# io-board-f-6.net
KiCad netlist of a schematic drawn in EAGLE
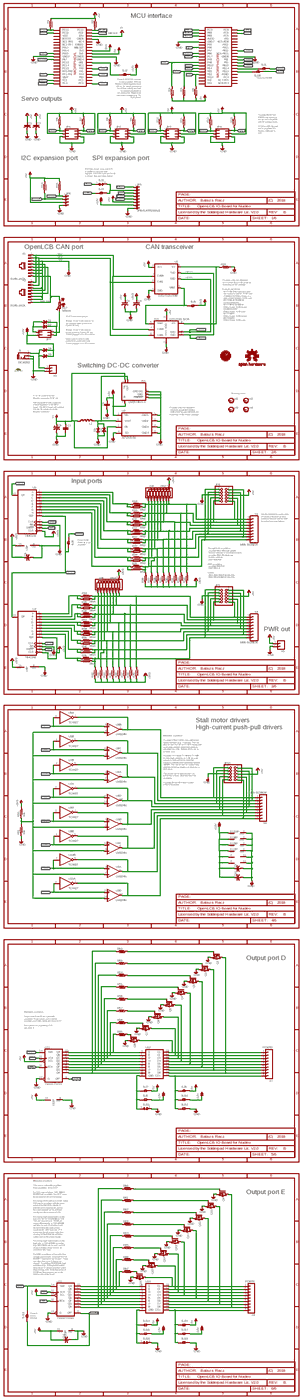
[diagram p0: schematic, sheet 1, overview]
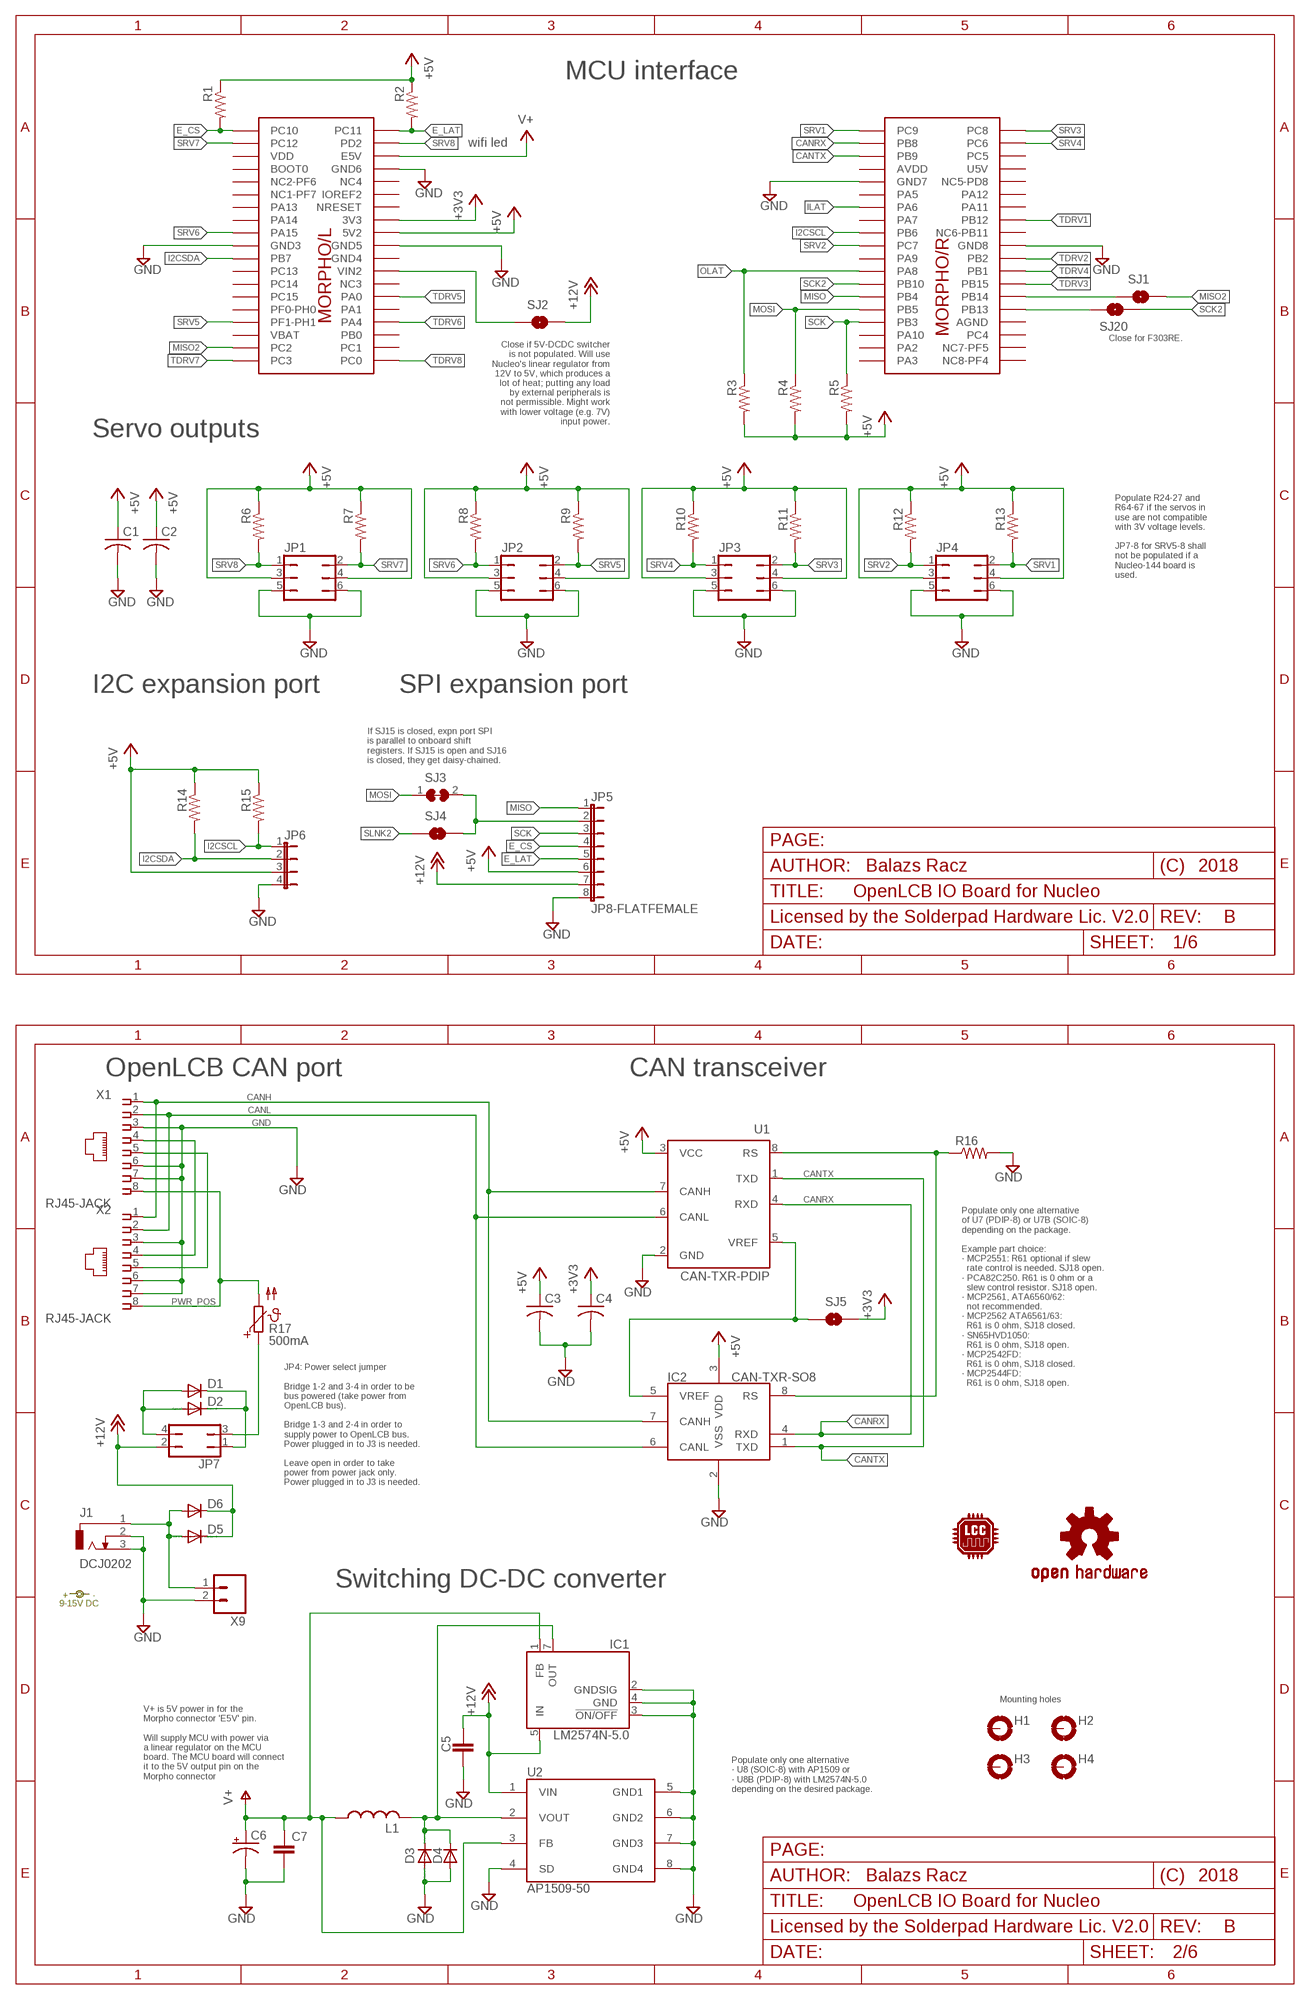
[diagram p1: schematic, sheet 1, part 1 of 4]
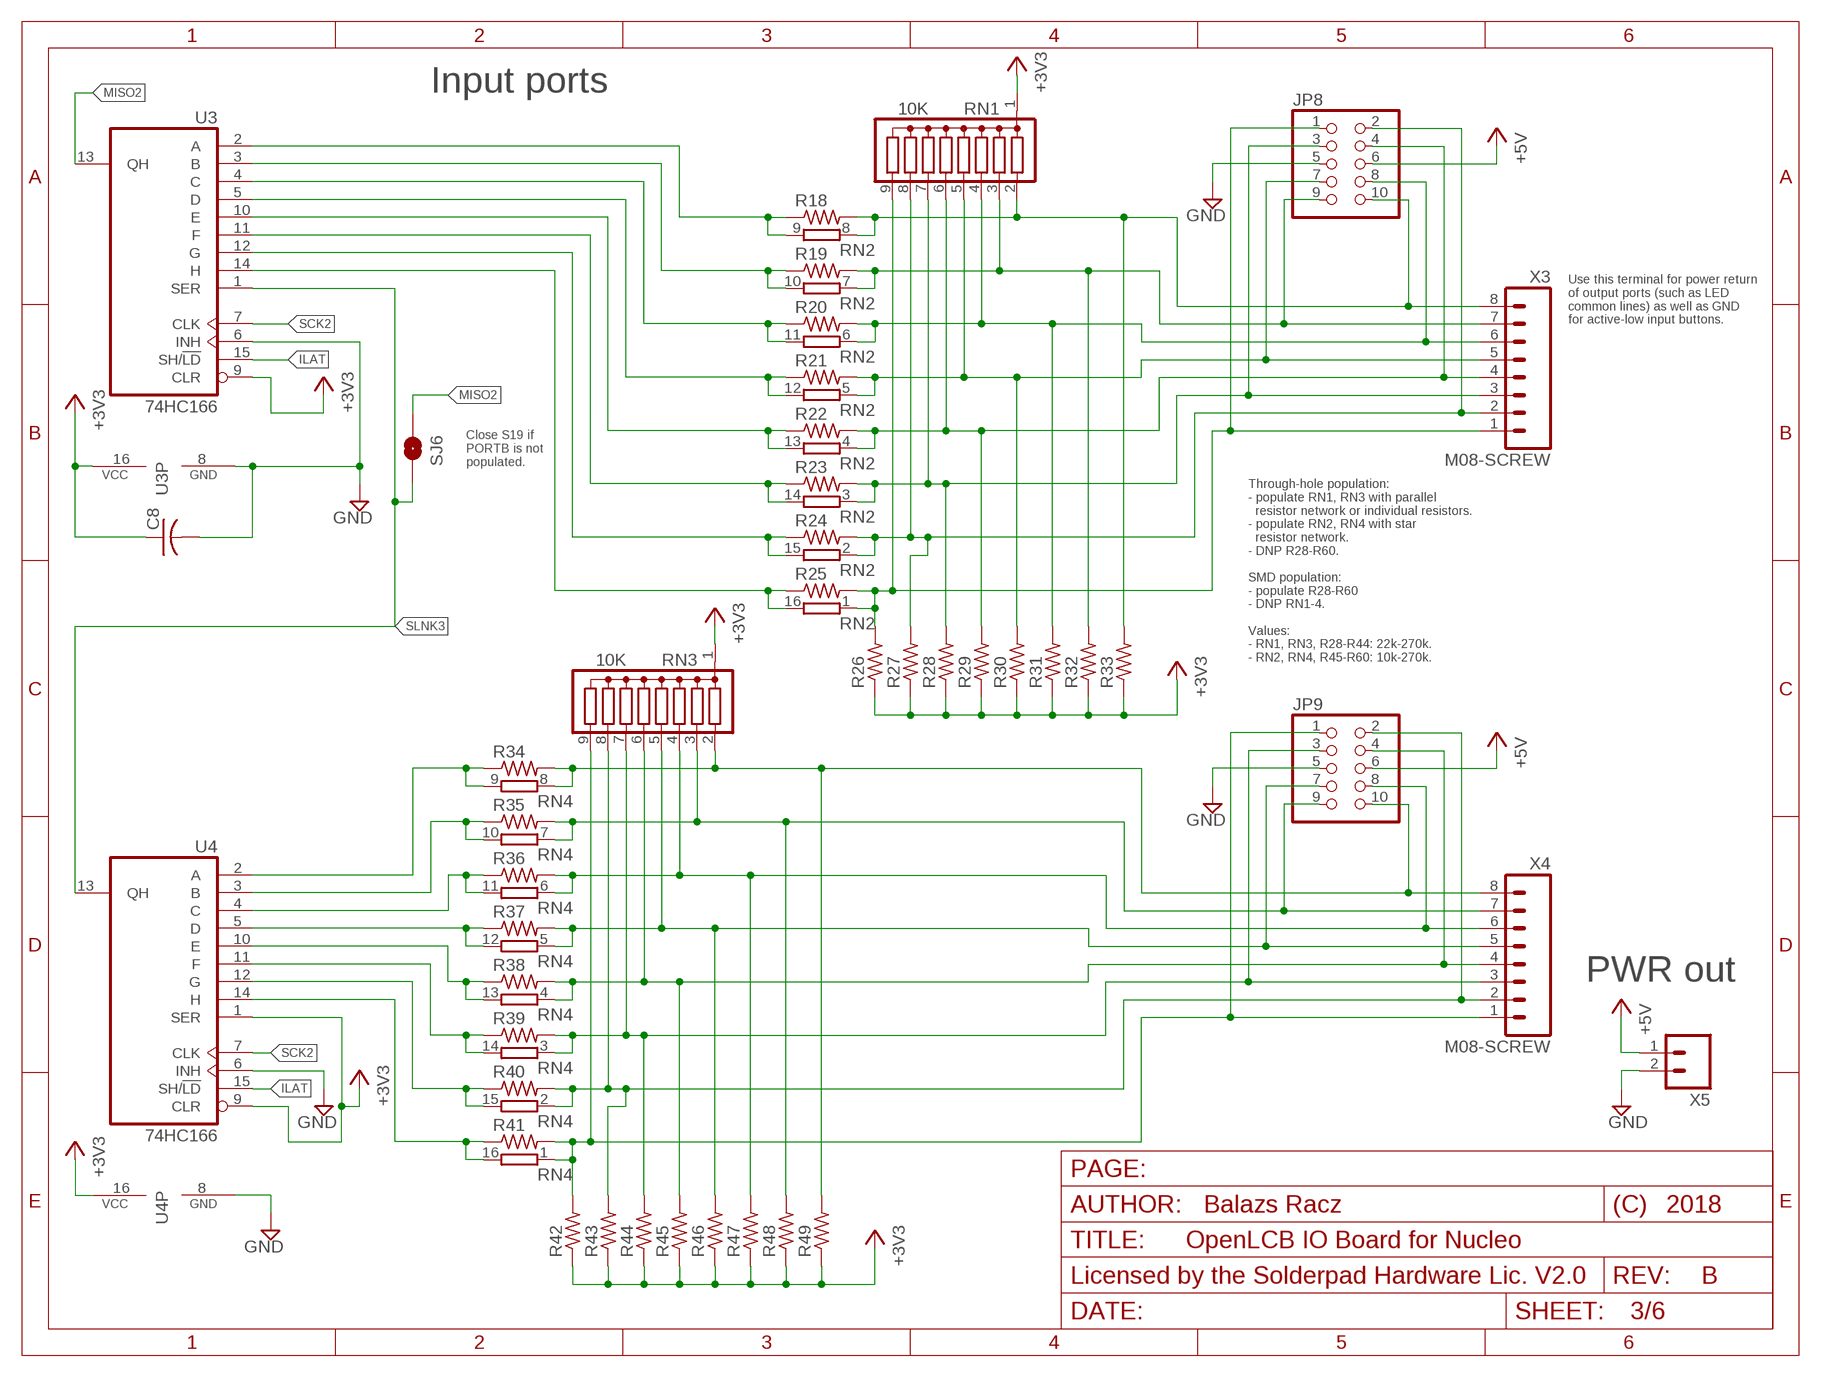
[diagram p2: schematic, sheet 1, part 2 of 4]
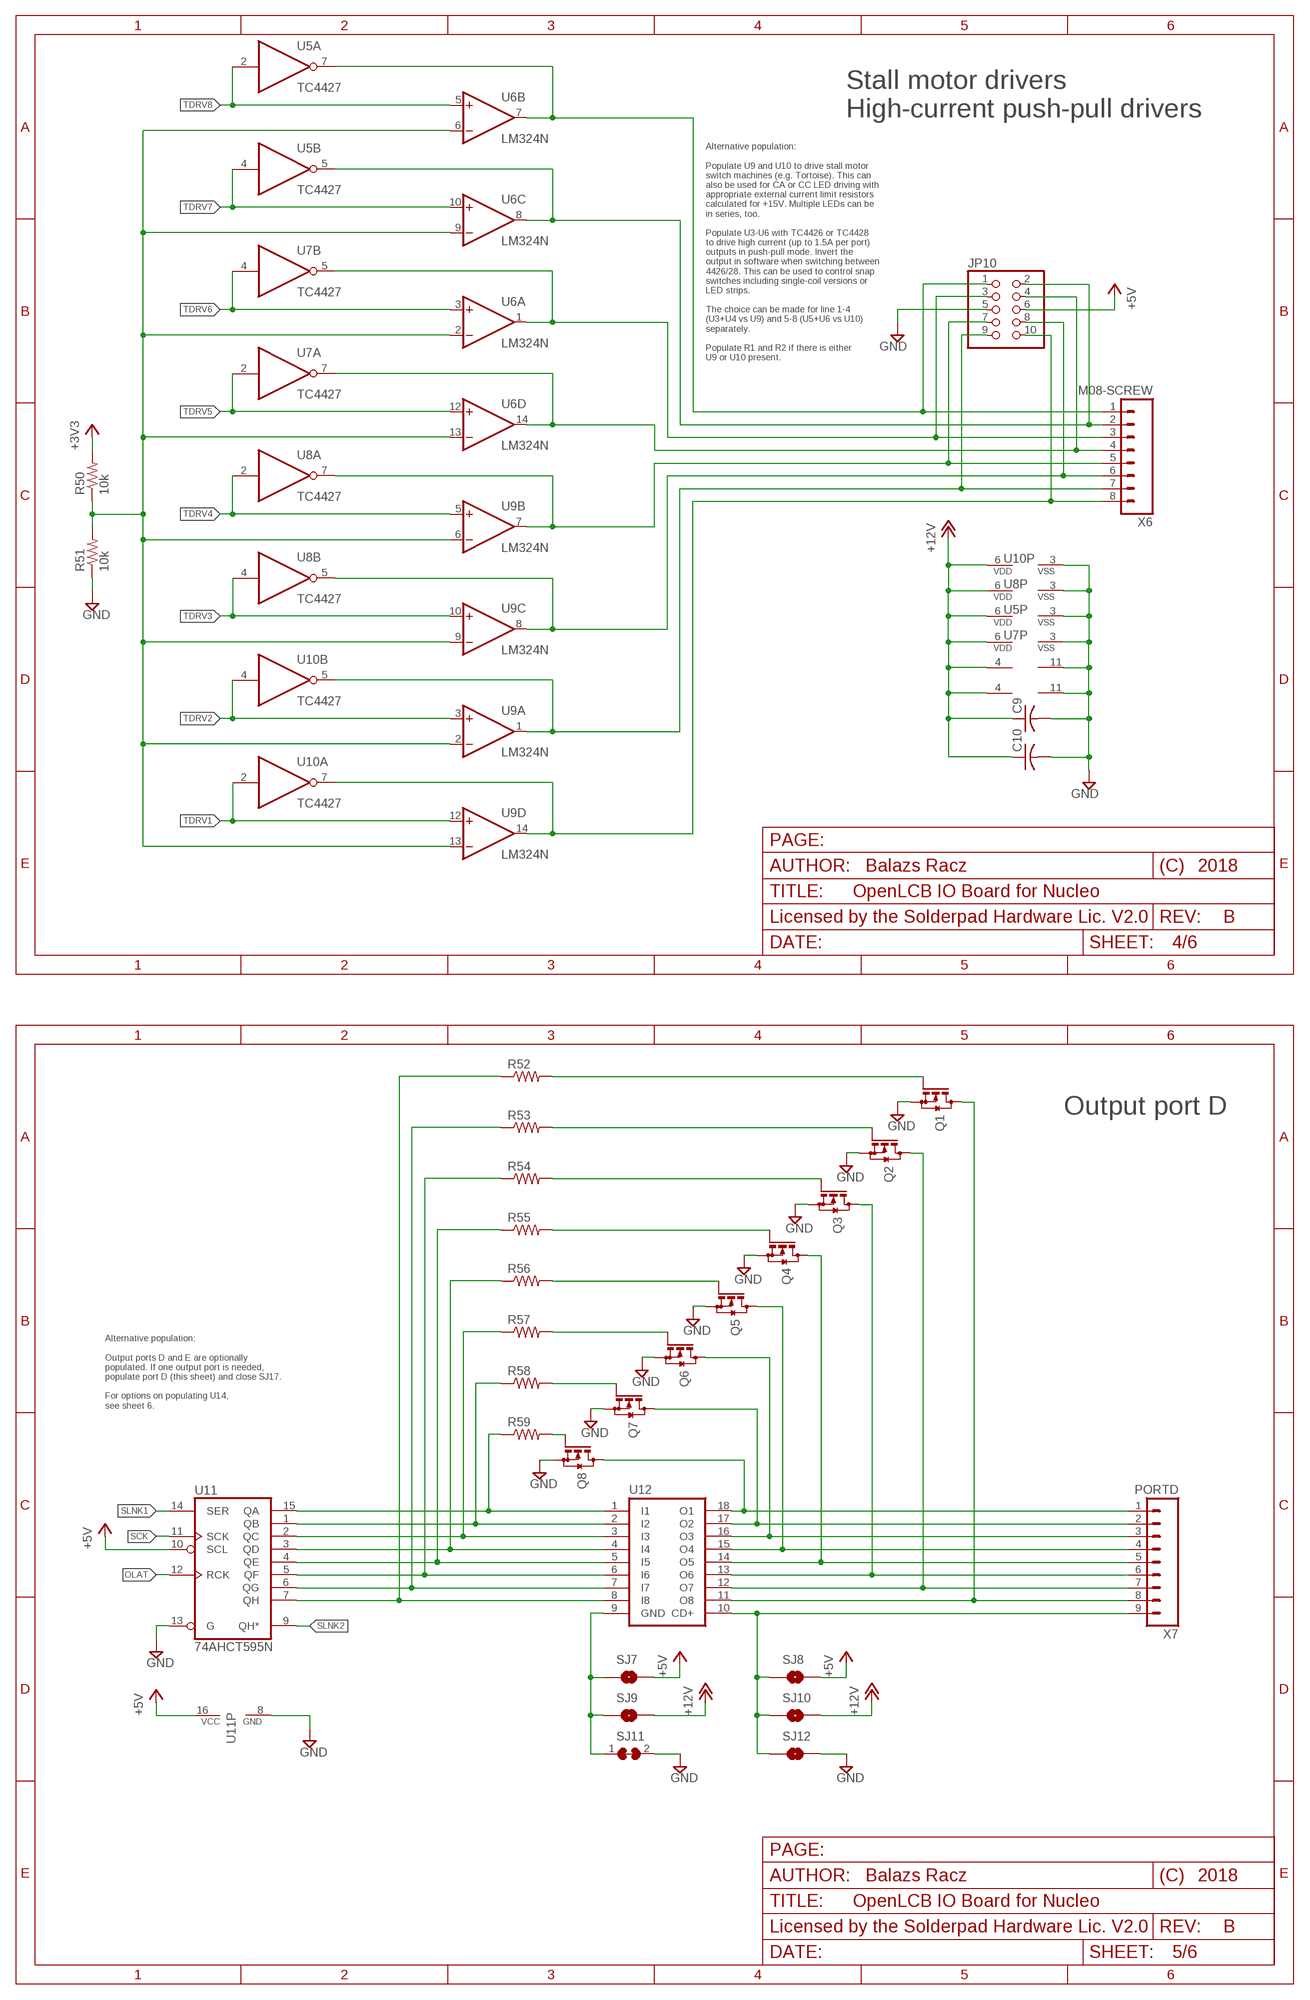
[diagram p3: schematic, sheet 1, part 3 of 4]
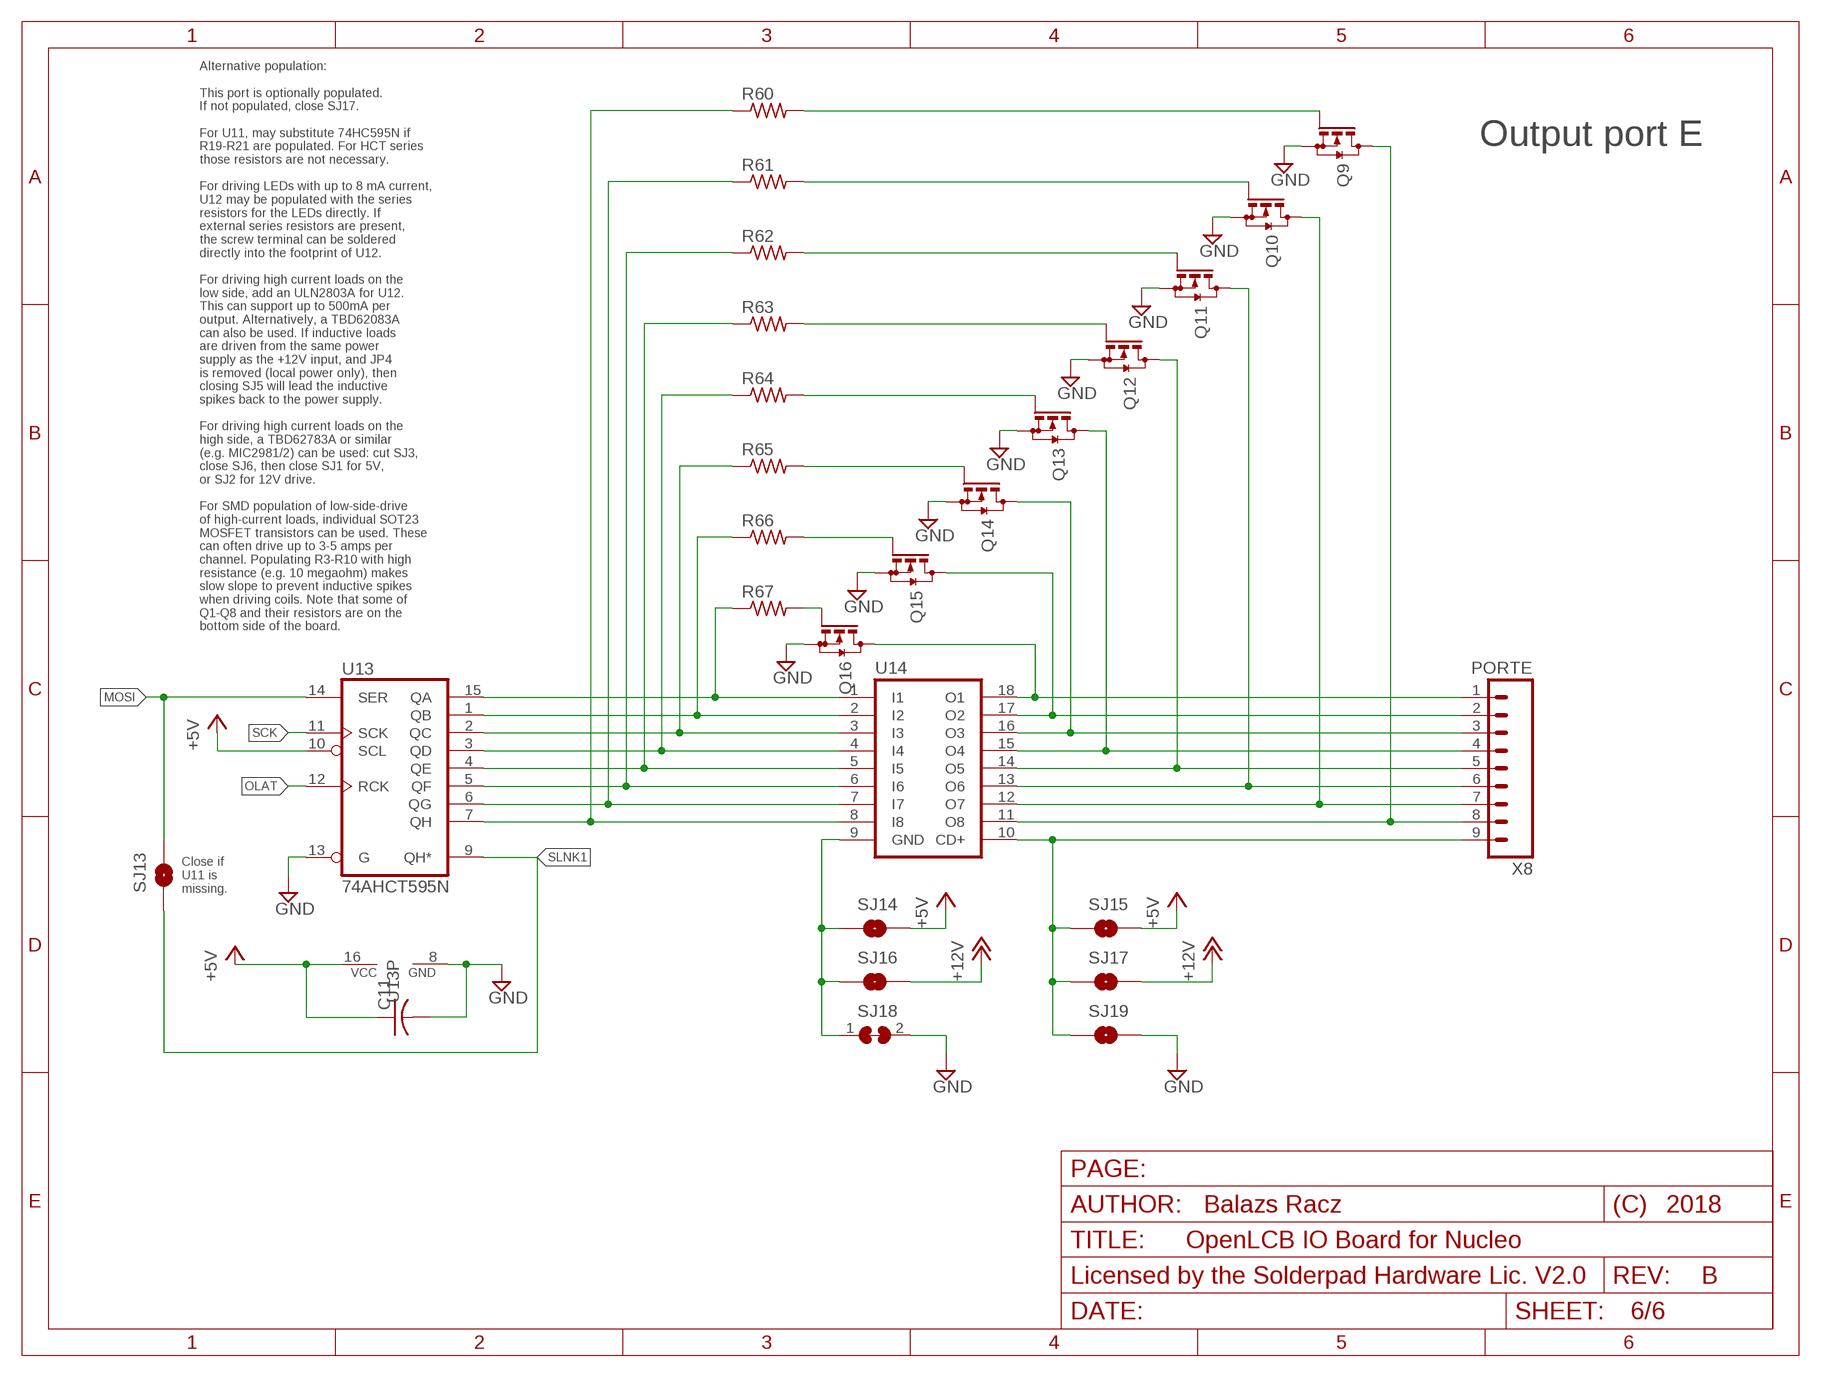
[diagram p4: schematic, sheet 1, part 4 of 4]

(export (version "E")
  (design (tool "Eeschema 10.0.6"))
  (components
    (comp (ref "C1")
      (value "C-USC1206")
      (footprint "eagle-import:C1206")
      (libsource (lib "eagle-import") (part "C-USC1206"))
    )
    (comp (ref "C2")
      (value "C-USC1206")
      (footprint "eagle-import:C1206")
      (libsource (lib "eagle-import") (part "C-USC1206"))
    )
    (comp (ref "C3")
      (value "C-USC0805")
      (footprint "eagle-import:C0805")
      (libsource (lib "eagle-import") (part "C-USC0805"))
    )
    (comp (ref "C4")
      (value "C-USC0805")
      (footprint "eagle-import:C0805")
      (libsource (lib "eagle-import") (part "C-USC0805"))
    )
    (comp (ref "C5")
      (value "C-EUC1206")
      (footprint "eagle-import:C1206")
      (libsource (lib "eagle-import") (part "C-EUC1206"))
    )
    (comp (ref "C6")
      (value "CPOL-USE2.5-5")
      (footprint "eagle-import:E2,5-5")
      (libsource (lib "eagle-import") (part "CPOL-USE2.5-5"))
    )
    (comp (ref "C7")
      (value "C-EUC1206")
      (footprint "eagle-import:C1206")
      (libsource (lib "eagle-import") (part "C-EUC1206"))
    )
    (comp (ref "C8")
      (value "C-USC0805")
      (footprint "eagle-import:C0805")
      (libsource (lib "eagle-import") (part "C-USC0805"))
    )
    (comp (ref "C9")
      (value "C-USC1206")
      (footprint "eagle-import:C1206")
      (libsource (lib "eagle-import") (part "C-USC1206"))
    )
    (comp (ref "C10")
      (value "C-USC1206")
      (footprint "eagle-import:C1206")
      (libsource (lib "eagle-import") (part "C-USC1206"))
    )
    (comp (ref "C11")
      (value "C-USC0805")
      (footprint "eagle-import:C0805")
      (libsource (lib "eagle-import") (part "C-USC0805"))
    )
    (comp (ref "D1")
      (value "DIODEDO-214AA-NODOC")
      (footprint "eagle-import:DO214AA-NODOC")
      (libsource (lib "eagle-import") (part "DIODEDO-214AA-NODOC"))
    )
    (comp (ref "D2")
      (value "DIODE-DO41-7.6")
      (footprint "eagle-import:DO41-7.6")
      (libsource (lib "eagle-import") (part "DIODE-DO41-7.6"))
    )
    (comp (ref "D3")
      (value "DIODE-DO41-7.6")
      (footprint "eagle-import:DO41-7.6")
      (libsource (lib "eagle-import") (part "DIODE-DO41-7.6"))
    )
    (comp (ref "D4")
      (value "DIODEDO-214AA-NODOC")
      (footprint "eagle-import:DO214AA-NODOC")
      (libsource (lib "eagle-import") (part "DIODEDO-214AA-NODOC"))
    )
    (comp (ref "D5")
      (value "DIODE-DO41-7.6")
      (footprint "eagle-import:DO41-7.6")
      (libsource (lib "eagle-import") (part "DIODE-DO41-7.6"))
    )
    (comp (ref "D6")
      (value "DIODEDO-214AA-NODOC")
      (footprint "eagle-import:DO214AA-NODOC")
      (libsource (lib "eagle-import") (part "DIODEDO-214AA-NODOC"))
    )
    (comp (ref "G1")
      (value "NUCLEO_64_GENERIC")
      (footprint "eagle-import:NUCLEO_BRD_BASE64")
      (libsource (lib "eagle-import") (part "NUCLEO_64_GENERIC"))
    )
    (comp (ref "H1")
      (value "MOUNT-PAD-ROUND3.3")
      (footprint "eagle-import:3,3-PAD")
      (libsource (lib "eagle-import") (part "MOUNT-PAD-ROUND3.3"))
    )
    (comp (ref "H2")
      (value "MOUNT-PAD-ROUND3.3")
      (footprint "eagle-import:3,3-PAD")
      (libsource (lib "eagle-import") (part "MOUNT-PAD-ROUND3.3"))
    )
    (comp (ref "H3")
      (value "MOUNT-PAD-ROUND3.3")
      (footprint "eagle-import:3,3-PAD")
      (libsource (lib "eagle-import") (part "MOUNT-PAD-ROUND3.3"))
    )
    (comp (ref "H4")
      (value "MOUNT-PAD-ROUND3.3")
      (footprint "eagle-import:3,3-PAD")
      (libsource (lib "eagle-import") (part "MOUNT-PAD-ROUND3.3"))
    )
    (comp (ref "IC1")
      (value "LM2574N-5.0")
      (footprint "eagle-import:DIL08")
      (libsource (lib "eagle-import") (part "LM2574?-N5.0"))
    )
    (comp (ref "IC2")
      (value "CAN-TXR-SO8")
      (footprint "eagle-import:SO-08")
      (libsource (lib "eagle-import") (part "MCP2551-SN"))
    )
    (comp (ref "J1")
      (value "DCJ0202")
      (footprint "eagle-import:DCJ0202")
      (libsource (lib "eagle-import") (part "DCJ0202"))
    )
    (comp (ref "JP1")
      (value "JP3Q")
      (footprint "eagle-import:JP3Q")
      (libsource (lib "eagle-import") (part "JP3Q"))
    )
    (comp (ref "JP2")
      (value "JP3Q")
      (footprint "eagle-import:JP3Q")
      (libsource (lib "eagle-import") (part "JP3Q"))
    )
    (comp (ref "JP3")
      (value "JP3Q")
      (footprint "eagle-import:JP3Q")
      (libsource (lib "eagle-import") (part "JP3Q"))
    )
    (comp (ref "JP4")
      (value "JP3Q")
      (footprint "eagle-import:JP3Q")
      (libsource (lib "eagle-import") (part "JP3Q"))
    )
    (comp (ref "JP5")
      (value "JP8-FLATFEMALE")
      (footprint "eagle-import:JP8F-FEM")
      (libsource (lib "eagle-import") (part "JP8-FLATFEMALE"))
    )
    (comp (ref "JP6")
      (value "JP4-FLAT")
      (footprint "eagle-import:JP4F")
      (libsource (lib "eagle-import") (part "JP4-FLAT"))
    )
    (comp (ref "JP7")
      (value "JP2Q")
      (footprint "eagle-import:JP2Q")
      (libsource (lib "eagle-import") (part "JP2Q"))
    )
    (comp (ref "JP8")
      (value "PINHD-2X5CN")
      (footprint "eagle-import:CON10M")
      (libsource (lib "eagle-import") (part "PINHD-2X5CN"))
    )
    (comp (ref "JP9")
      (value "PINHD-2X5CN")
      (footprint "eagle-import:CON10M")
      (libsource (lib "eagle-import") (part "PINHD-2X5CN"))
    )
    (comp (ref "JP10")
      (value "PINHD-2X5CN")
      (footprint "eagle-import:CON10M")
      (libsource (lib "eagle-import") (part "PINHD-2X5CN"))
    )
    (comp (ref "L1")
      (value "L-US")
      (footprint "eagle-import:L5-8,5")
      (libsource (lib "eagle-import") (part "L-US"))
    )
    (comp (ref "LG1")
      (value "LCC_LOGO")
      (footprint "eagle-import:LCC_LOGO")
      (libsource (lib "eagle-import") (part "LCC_LOGO"))
    )
    (comp (ref "LOGO1")
      (value "DOC-OSHW-LOGOM")
      (footprint "eagle-import:OSHW-LOGO-M")
      (libsource (lib "eagle-import") (part "DOC-OSHW-LOGOM"))
    )
    (comp (ref "P1")
      (value "9-15V DC")
      (footprint "eagle-import:POWER_USAGE")
      (libsource (lib "eagle-import") (part "DOC-POWER_LABEL"))
    )
    (comp (ref "Q1")
      (value "BSS123")
      (footprint "eagle-import:SOT23")
      (libsource (lib "eagle-import") (part "BSS123"))
    )
    (comp (ref "Q2")
      (value "BSS123")
      (footprint "eagle-import:SOT23")
      (libsource (lib "eagle-import") (part "BSS123"))
    )
    (comp (ref "Q3")
      (value "BSS123")
      (footprint "eagle-import:SOT23")
      (libsource (lib "eagle-import") (part "BSS123"))
    )
    (comp (ref "Q4")
      (value "BSS123")
      (footprint "eagle-import:SOT23")
      (libsource (lib "eagle-import") (part "BSS123"))
    )
    (comp (ref "Q5")
      (value "BSS123")
      (footprint "eagle-import:SOT23")
      (libsource (lib "eagle-import") (part "BSS123"))
    )
    (comp (ref "Q6")
      (value "BSS123")
      (footprint "eagle-import:SOT23")
      (libsource (lib "eagle-import") (part "BSS123"))
    )
    (comp (ref "Q7")
      (value "BSS123")
      (footprint "eagle-import:SOT23")
      (libsource (lib "eagle-import") (part "BSS123"))
    )
    (comp (ref "Q8")
      (value "BSS123")
      (footprint "eagle-import:SOT23")
      (libsource (lib "eagle-import") (part "BSS123"))
    )
    (comp (ref "Q9")
      (value "BSS123")
      (footprint "eagle-import:SOT23")
      (libsource (lib "eagle-import") (part "BSS123"))
    )
    (comp (ref "Q10")
      (value "BSS123")
      (footprint "eagle-import:SOT23")
      (libsource (lib "eagle-import") (part "BSS123"))
    )
    (comp (ref "Q11")
      (value "BSS123")
      (footprint "eagle-import:SOT23")
      (libsource (lib "eagle-import") (part "BSS123"))
    )
    (comp (ref "Q12")
      (value "BSS123")
      (footprint "eagle-import:SOT23")
      (libsource (lib "eagle-import") (part "BSS123"))
    )
    (comp (ref "Q13")
      (value "BSS123")
      (footprint "eagle-import:SOT23")
      (libsource (lib "eagle-import") (part "BSS123"))
    )
    (comp (ref "Q14")
      (value "BSS123")
      (footprint "eagle-import:SOT23")
      (libsource (lib "eagle-import") (part "BSS123"))
    )
    (comp (ref "Q15")
      (value "BSS123")
      (footprint "eagle-import:SOT23")
      (libsource (lib "eagle-import") (part "BSS123"))
    )
    (comp (ref "Q16")
      (value "BSS123")
      (footprint "eagle-import:SOT23")
      (libsource (lib "eagle-import") (part "BSS123"))
    )
    (comp (ref "R1")
      (value "R-US_R0805")
      (footprint "eagle-import:R0805")
      (libsource (lib "eagle-import") (part "rcl_334_R-US_R0805"))
    )
    (comp (ref "R2")
      (value "R-US_R0805")
      (footprint "eagle-import:R0805")
      (libsource (lib "eagle-import") (part "rcl_334_R-US_R0805"))
    )
    (comp (ref "R3")
      (value "R-US_R0805")
      (footprint "eagle-import:R0805")
      (libsource (lib "eagle-import") (part "rcl_334_R-US_R0805"))
    )
    (comp (ref "R4")
      (value "R-US_R0805")
      (footprint "eagle-import:R0805")
      (libsource (lib "eagle-import") (part "rcl_334_R-US_R0805"))
    )
    (comp (ref "R5")
      (value "R-US_R0805")
      (footprint "eagle-import:R0805")
      (libsource (lib "eagle-import") (part "rcl_334_R-US_R0805"))
    )
    (comp (ref "R6")
      (value "R-US_R0805")
      (footprint "eagle-import:R0805")
      (libsource (lib "eagle-import") (part "rcl_334_R-US_R0805"))
    )
    (comp (ref "R7")
      (value "R-US_R0805")
      (footprint "eagle-import:R0805")
      (libsource (lib "eagle-import") (part "rcl_334_R-US_R0805"))
    )
    (comp (ref "R8")
      (value "R-US_R0805")
      (footprint "eagle-import:R0805")
      (libsource (lib "eagle-import") (part "rcl_334_R-US_R0805"))
    )
    (comp (ref "R9")
      (value "R-US_R0805")
      (footprint "eagle-import:R0805")
      (libsource (lib "eagle-import") (part "rcl_334_R-US_R0805"))
    )
    (comp (ref "R10")
      (value "R-US_R0805")
      (footprint "eagle-import:R0805")
      (libsource (lib "eagle-import") (part "rcl_334_R-US_R0805"))
    )
    (comp (ref "R11")
      (value "R-US_R0805")
      (footprint "eagle-import:R0805")
      (libsource (lib "eagle-import") (part "rcl_334_R-US_R0805"))
    )
    (comp (ref "R12")
      (value "R-US_R0805")
      (footprint "eagle-import:R0805")
      (libsource (lib "eagle-import") (part "rcl_334_R-US_R0805"))
    )
    (comp (ref "R13")
      (value "R-US_R0805")
      (footprint "eagle-import:R0805")
      (libsource (lib "eagle-import") (part "rcl_334_R-US_R0805"))
    )
    (comp (ref "R14")
      (value "R-US_R0805")
      (footprint "eagle-import:R0805")
      (libsource (lib "eagle-import") (part "rcl_334_R-US_R0805"))
    )
    (comp (ref "R15")
      (value "R-US_R0805")
      (footprint "eagle-import:R0805")
      (libsource (lib "eagle-import") (part "rcl_334_R-US_R0805"))
    )
    (comp (ref "R16")
      (value "R-US_R0805")
      (footprint "eagle-import:R0805")
      (libsource (lib "eagle-import") (part "rcl_334_R-US_R0805"))
    )
    (comp (ref "R17")
      (value "500mA")
      (footprint "eagle-import:PTC1812")
      (libsource (lib "eagle-import") (part "PTC_1812"))
    )
    (comp (ref "R18")
      (value "R-US_R0603")
      (footprint "eagle-import:R0603")
      (libsource (lib "eagle-import") (part "rcl_334_R-US_R0603"))
    )
    (comp (ref "R19")
      (value "R-US_R0603")
      (footprint "eagle-import:R0603")
      (libsource (lib "eagle-import") (part "rcl_334_R-US_R0603"))
    )
    (comp (ref "R20")
      (value "R-US_R0603")
      (footprint "eagle-import:R0603")
      (libsource (lib "eagle-import") (part "rcl_334_R-US_R0603"))
    )
    (comp (ref "R21")
      (value "R-US_R0603")
      (footprint "eagle-import:R0603")
      (libsource (lib "eagle-import") (part "rcl_334_R-US_R0603"))
    )
    (comp (ref "R22")
      (value "R-US_R0603")
      (footprint "eagle-import:R0603")
      (libsource (lib "eagle-import") (part "rcl_334_R-US_R0603"))
    )
    (comp (ref "R23")
      (value "R-US_R0603")
      (footprint "eagle-import:R0603")
      (libsource (lib "eagle-import") (part "rcl_334_R-US_R0603"))
    )
    (comp (ref "R24")
      (value "R-US_R0603")
      (footprint "eagle-import:R0603")
      (libsource (lib "eagle-import") (part "rcl_334_R-US_R0603"))
    )
    (comp (ref "R25")
      (value "R-US_R0603")
      (footprint "eagle-import:R0603")
      (libsource (lib "eagle-import") (part "rcl_334_R-US_R0603"))
    )
    (comp (ref "R26")
      (value "R-US")
      (footprint "eagle-import:R0603")
      (libsource (lib "eagle-import") (part "R-US"))
    )
    (comp (ref "R27")
      (value "R-US")
      (footprint "eagle-import:R0603")
      (libsource (lib "eagle-import") (part "R-US"))
    )
    (comp (ref "R28")
      (value "R-US")
      (footprint "eagle-import:R0603")
      (libsource (lib "eagle-import") (part "R-US"))
    )
    (comp (ref "R29")
      (value "R-US")
      (footprint "eagle-import:R0603")
      (libsource (lib "eagle-import") (part "R-US"))
    )
    (comp (ref "R30")
      (value "R-US")
      (footprint "eagle-import:R0603")
      (libsource (lib "eagle-import") (part "R-US"))
    )
    (comp (ref "R31")
      (value "R-US")
      (footprint "eagle-import:R0603")
      (libsource (lib "eagle-import") (part "R-US"))
    )
    (comp (ref "R32")
      (value "R-US")
      (footprint "eagle-import:R0603")
      (libsource (lib "eagle-import") (part "R-US"))
    )
    (comp (ref "R33")
      (value "R-US")
      (footprint "eagle-import:R0603")
      (libsource (lib "eagle-import") (part "R-US"))
    )
    (comp (ref "R34")
      (value "R-US_R0603")
      (footprint "eagle-import:R0603")
      (libsource (lib "eagle-import") (part "rcl_334_R-US_R0603"))
    )
    (comp (ref "R35")
      (value "R-US_R0603")
      (footprint "eagle-import:R0603")
      (libsource (lib "eagle-import") (part "rcl_334_R-US_R0603"))
    )
    (comp (ref "R36")
      (value "R-US_R0603")
      (footprint "eagle-import:R0603")
      (libsource (lib "eagle-import") (part "rcl_334_R-US_R0603"))
    )
    (comp (ref "R37")
      (value "R-US_R0603")
      (footprint "eagle-import:R0603")
      (libsource (lib "eagle-import") (part "rcl_334_R-US_R0603"))
    )
    (comp (ref "R38")
      (value "R-US_R0603")
      (footprint "eagle-import:R0603")
      (libsource (lib "eagle-import") (part "rcl_334_R-US_R0603"))
    )
    (comp (ref "R39")
      (value "R-US_R0603")
      (footprint "eagle-import:R0603")
      (libsource (lib "eagle-import") (part "rcl_334_R-US_R0603"))
    )
    (comp (ref "R40")
      (value "R-US_R0603")
      (footprint "eagle-import:R0603")
      (libsource (lib "eagle-import") (part "rcl_334_R-US_R0603"))
    )
    (comp (ref "R41")
      (value "R-US_R0603")
      (footprint "eagle-import:R0603")
      (libsource (lib "eagle-import") (part "rcl_334_R-US_R0603"))
    )
    (comp (ref "R42")
      (value "R-US")
      (footprint "eagle-import:R0603")
      (libsource (lib "eagle-import") (part "R-US"))
    )
    (comp (ref "R43")
      (value "R-US")
      (footprint "eagle-import:R0603")
      (libsource (lib "eagle-import") (part "R-US"))
    )
    (comp (ref "R44")
      (value "R-US")
      (footprint "eagle-import:R0603")
      (libsource (lib "eagle-import") (part "R-US"))
    )
    (comp (ref "R45")
      (value "R-US")
      (footprint "eagle-import:R0603")
      (libsource (lib "eagle-import") (part "R-US"))
    )
    (comp (ref "R46")
      (value "R-US")
      (footprint "eagle-import:R0603")
      (libsource (lib "eagle-import") (part "R-US"))
    )
    (comp (ref "R47")
      (value "R-US")
      (footprint "eagle-import:R0603")
      (libsource (lib "eagle-import") (part "R-US"))
    )
    (comp (ref "R48")
      (value "R-US")
      (footprint "eagle-import:R0603")
      (libsource (lib "eagle-import") (part "R-US"))
    )
    (comp (ref "R49")
      (value "R-US")
      (footprint "eagle-import:R0603")
      (libsource (lib "eagle-import") (part "R-US"))
    )
    (comp (ref "R50")
      (value "10k")
      (footprint "eagle-import:R0805")
      (libsource (lib "eagle-import") (part "R-US_R0805"))
    )
    (comp (ref "R51")
      (value "10k")
      (footprint "eagle-import:R0805")
      (libsource (lib "eagle-import") (part "R-US_R0805"))
    )
    (comp (ref "R52")
      (value "R-US_R0603")
      (footprint "eagle-import:R0603")
      (libsource (lib "eagle-import") (part "R-US_R0603"))
    )
    (comp (ref "R53")
      (value "R-US_R0603")
      (footprint "eagle-import:R0603")
      (libsource (lib "eagle-import") (part "R-US_R0603"))
    )
    (comp (ref "R54")
      (value "R-US_R0603")
      (footprint "eagle-import:R0603")
      (libsource (lib "eagle-import") (part "R-US_R0603"))
    )
    (comp (ref "R55")
      (value "R-US_R0603")
      (footprint "eagle-import:R0603")
      (libsource (lib "eagle-import") (part "R-US_R0603"))
    )
    (comp (ref "R56")
      (value "R-US_R0603")
      (footprint "eagle-import:R0603")
      (libsource (lib "eagle-import") (part "R-US_R0603"))
    )
    (comp (ref "R57")
      (value "R-US_R0603")
      (footprint "eagle-import:R0603")
      (libsource (lib "eagle-import") (part "R-US_R0603"))
    )
    (comp (ref "R58")
      (value "R-US_R0603")
      (footprint "eagle-import:R0603")
      (libsource (lib "eagle-import") (part "R-US_R0603"))
    )
    (comp (ref "R59")
      (value "R-US_R0603")
      (footprint "eagle-import:R0603")
      (libsource (lib "eagle-import") (part "R-US_R0603"))
    )
    (comp (ref "R60")
      (value "R-US_R0603")
      (footprint "eagle-import:R0603")
      (libsource (lib "eagle-import") (part "R-US_R0603"))
    )
    (comp (ref "R61")
      (value "R-US_R0603")
      (footprint "eagle-import:R0603")
      (libsource (lib "eagle-import") (part "R-US_R0603"))
    )
    (comp (ref "R62")
      (value "R-US_R0603")
      (footprint "eagle-import:R0603")
      (libsource (lib "eagle-import") (part "R-US_R0603"))
    )
    (comp (ref "R63")
      (value "R-US_R0603")
      (footprint "eagle-import:R0603")
      (libsource (lib "eagle-import") (part "R-US_R0603"))
    )
    (comp (ref "R64")
      (value "R-US_R0603")
      (footprint "eagle-import:R0603")
      (libsource (lib "eagle-import") (part "R-US_R0603"))
    )
    (comp (ref "R65")
      (value "R-US_R0603")
      (footprint "eagle-import:R0603")
      (libsource (lib "eagle-import") (part "R-US_R0603"))
    )
    (comp (ref "R66")
      (value "R-US_R0603")
      (footprint "eagle-import:R0603")
      (libsource (lib "eagle-import") (part "R-US_R0603"))
    )
    (comp (ref "R67")
      (value "R-US_R0603")
      (footprint "eagle-import:R0603")
      (libsource (lib "eagle-import") (part "R-US_R0603"))
    )
    (comp (ref "RN1")
      (value "10K")
      (footprint "eagle-import:SIL9")
      (libsource (lib "eagle-import") (part "G08R"))
    )
    (comp (ref "RN2")
      (value "8R-P")
      (footprint "eagle-import:DIL16")
      (libsource (lib "eagle-import") (part "8R-P"))
    )
    (comp (ref "RN3")
      (value "10K")
      (footprint "eagle-import:SIL9")
      (libsource (lib "eagle-import") (part "G08R"))
    )
    (comp (ref "RN4")
      (value "8R-P")
      (footprint "eagle-import:DIL16")
      (libsource (lib "eagle-import") (part "8R-P"))
    )
    (comp (ref "SJ1")
      (value "SJRND2")
      (footprint "eagle-import:SJ_RND2")
      (libsource (lib "eagle-import") (part "SJRND2"))
    )
    (comp (ref "SJ2")
      (value "SJRND2")
      (footprint "eagle-import:SJ_RND2")
      (libsource (lib "eagle-import") (part "SJRND2"))
    )
    (comp (ref "SJ3")
      (value "SJ-C")
      (footprint "eagle-import:SJW-C")
      (libsource (lib "eagle-import") (part "SJ-C"))
    )
    (comp (ref "SJ4")
      (value "SJRND2")
      (footprint "eagle-import:SJ_RND2")
      (libsource (lib "eagle-import") (part "SJRND2"))
    )
    (comp (ref "SJ5")
      (value "SJRND2")
      (footprint "eagle-import:SJ_RND2")
      (libsource (lib "eagle-import") (part "SJRND2"))
    )
    (comp (ref "SJ6")
      (value "SJRND2")
      (footprint "eagle-import:SJ_RND2")
      (libsource (lib "eagle-import") (part "SJRND2"))
    )
    (comp (ref "SJ7")
      (value "SJRND2")
      (footprint "eagle-import:SJ_RND2")
      (libsource (lib "eagle-import") (part "SJRND2"))
    )
    (comp (ref "SJ8")
      (value "SJRND2")
      (footprint "eagle-import:SJ_RND2")
      (libsource (lib "eagle-import") (part "SJRND2"))
    )
    (comp (ref "SJ9")
      (value "SJRND2")
      (footprint "eagle-import:SJ_RND2")
      (libsource (lib "eagle-import") (part "SJRND2"))
    )
    (comp (ref "SJ10")
      (value "SJRND2")
      (footprint "eagle-import:SJ_RND2")
      (libsource (lib "eagle-import") (part "SJRND2"))
    )
    (comp (ref "SJ11")
      (value "SJ-C")
      (footprint "eagle-import:SJW-C")
      (libsource (lib "eagle-import") (part "SJ-C"))
    )
    (comp (ref "SJ12")
      (value "SJRND2")
      (footprint "eagle-import:SJ_RND2")
      (libsource (lib "eagle-import") (part "SJRND2"))
    )
    (comp (ref "SJ13")
      (value "SJRND2")
      (footprint "eagle-import:SJ_RND2")
      (libsource (lib "eagle-import") (part "SJRND2"))
    )
    (comp (ref "SJ14")
      (value "SJRND2")
      (footprint "eagle-import:SJ_RND2")
      (libsource (lib "eagle-import") (part "SJRND2"))
    )
    (comp (ref "SJ15")
      (value "SJRND2")
      (footprint "eagle-import:SJ_RND2")
      (libsource (lib "eagle-import") (part "SJRND2"))
    )
    (comp (ref "SJ16")
      (value "SJRND2")
      (footprint "eagle-import:SJ_RND2")
      (libsource (lib "eagle-import") (part "SJRND2"))
    )
    (comp (ref "SJ17")
      (value "SJRND2")
      (footprint "eagle-import:SJ_RND2")
      (libsource (lib "eagle-import") (part "SJRND2"))
    )
    (comp (ref "SJ18")
      (value "SJ-C")
      (footprint "eagle-import:SJW-C")
      (libsource (lib "eagle-import") (part "SJ-C"))
    )
    (comp (ref "SJ19")
      (value "SJRND2")
      (footprint "eagle-import:SJ_RND2")
      (libsource (lib "eagle-import") (part "SJRND2"))
    )
    (comp (ref "SJ20")
      (value "SJRND2")
      (footprint "eagle-import:SJ_RND2")
      (libsource (lib "eagle-import") (part "SJRND2"))
    )
    (comp (ref "U1")
      (value "CAN-TXR-PDIP")
      (footprint "eagle-import:DIL08")
      (libsource (lib "eagle-import") (part "PCA82C250"))
    )
    (comp (ref "U2")
      (value "AP1509-50")
      (footprint "eagle-import:SO-08")
      (libsource (lib "eagle-import") (part "AP1509"))
    )
    (comp (ref "U3")
      (value "74HC166")
      (footprint "eagle-import:DIL16")
      (libsource (lib "eagle-import") (part "74166N"))
    )
    (comp (ref "U4")
      (value "74HC166")
      (footprint "eagle-import:DIL16")
      (libsource (lib "eagle-import") (part "74166N"))
    )
    (comp (ref "U5")
      (value "TC4427")
      (footprint "eagle-import:DIL08-LONG")
      (libsource (lib "eagle-import") (part "TC4426APDIP"))
    )
    (comp (ref "U6")
      (value "LM324N")
      (footprint "eagle-import:DIL14")
      (libsource (lib "eagle-import") (part "LM324N"))
    )
    (comp (ref "U7")
      (value "TC4427")
      (footprint "eagle-import:DIL08-LONG")
      (libsource (lib "eagle-import") (part "TC4426APDIP"))
    )
    (comp (ref "U8")
      (value "TC4427")
      (footprint "eagle-import:DIL08-LONG")
      (libsource (lib "eagle-import") (part "TC4426APDIP"))
    )
    (comp (ref "U9")
      (value "LM324N")
      (footprint "eagle-import:DIL14")
      (libsource (lib "eagle-import") (part "LM324N"))
    )
    (comp (ref "U10")
      (value "TC4427")
      (footprint "eagle-import:DIL08-LONG")
      (libsource (lib "eagle-import") (part "TC4426APDIP"))
    )
    (comp (ref "U11")
      (value "74AHCT595N")
      (footprint "eagle-import:DIL16")
      (libsource (lib "eagle-import") (part "74595NHCT"))
    )
    (comp (ref "U12")
      (value "ULN2803A")
      (footprint "eagle-import:DIL18-THIN")
      (libsource (lib "eagle-import") (part "ULN2803A"))
    )
    (comp (ref "U13")
      (value "74AHCT595N")
      (footprint "eagle-import:DIL16")
      (libsource (lib "eagle-import") (part "74595NHCT"))
    )
    (comp (ref "U14")
      (value "ULN2803A")
      (footprint "eagle-import:DIL18-THIN")
      (libsource (lib "eagle-import") (part "ULN2803A"))
    )
    (comp (ref "X1")
      (value "RJ45-JACK")
      (footprint "eagle-import:RJ45-PULSE-E5J88")
      (libsource (lib "eagle-import") (part "RJ45-JACKRJ45-PULSE-E5J00"))
    )
    (comp (ref "X2")
      (value "RJ45-JACK")
      (footprint "eagle-import:RJ45-PULSE-E5J88")
      (libsource (lib "eagle-import") (part "RJ45-JACKRJ45-PULSE-E5J00"))
    )
    (comp (ref "X3")
      (value "M08-SCREW")
      (footprint "eagle-import:1X08_TERMINAL")
      (libsource (lib "eagle-import") (part "M08-SCREW"))
    )
    (comp (ref "X4")
      (value "M08-SCREW")
      (footprint "eagle-import:1X08_TERMINAL")
      (libsource (lib "eagle-import") (part "M08-SCREW"))
    )
    (comp (ref "X5")
      (value "CONNECTOR-M023.5MM-LOCK")
      (footprint "eagle-import:SCREWTERMINAL-3.5MM-2_LOCK")
      (libsource (lib "eagle-import") (part "CONNECTOR-M023.5MM-LOCK"))
    )
    (comp (ref "X6")
      (value "M08-SCREW")
      (footprint "eagle-import:1X08_TERMINAL")
      (libsource (lib "eagle-import") (part "M08-SCREW"))
    )
    (comp (ref "X7")
      (value "PORTD")
      (footprint "eagle-import:1X09_TERMINAL")
      (libsource (lib "eagle-import") (part "M09-SCREW"))
    )
    (comp (ref "X8")
      (value "PORTE")
      (footprint "eagle-import:1X09_TERMINAL")
      (libsource (lib "eagle-import") (part "M09-SCREW"))
    )
    (comp (ref "X9")
      (value "CONNECTOR-M023.5MM-LOCK")
      (footprint "eagle-import:SCREWTERMINAL-3.5MM-2_LOCK")
      (libsource (lib "eagle-import") (part "CONNECTOR-M023.5MM-LOCK"))
    )
  )
  (nets
    (net (code "1") (name "+3V3") (class "Default")
      (node (ref "C4") (pin "1") (pinfunction "1_1") (pintype "passive"))
      (node (ref "C8") (pin "1") (pinfunction "1_1") (pintype "passive"))
      (node (ref "G1") (pin "3V3") (pinfunction "3V3_3V3") (pintype "power_in"))
      (node (ref "R26") (pin "1") (pinfunction "1_1") (pintype "passive"))
      (node (ref "R27") (pin "1") (pinfunction "1_1") (pintype "passive"))
      (node (ref "R28") (pin "1") (pinfunction "1_1") (pintype "passive"))
      (node (ref "R29") (pin "1") (pinfunction "1_1") (pintype "passive"))
      (node (ref "R30") (pin "1") (pinfunction "1_1") (pintype "passive"))
      (node (ref "R31") (pin "1") (pinfunction "1_1") (pintype "passive"))
      (node (ref "R32") (pin "1") (pinfunction "1_1") (pintype "passive"))
      (node (ref "R33") (pin "1") (pinfunction "1_1") (pintype "passive"))
      (node (ref "R42") (pin "1") (pinfunction "1_1") (pintype "passive"))
      (node (ref "R43") (pin "1") (pinfunction "1_1") (pintype "passive"))
      (node (ref "R44") (pin "1") (pinfunction "1_1") (pintype "passive"))
      (node (ref "R45") (pin "1") (pinfunction "1_1") (pintype "passive"))
      (node (ref "R46") (pin "1") (pinfunction "1_1") (pintype "passive"))
      (node (ref "R47") (pin "1") (pinfunction "1_1") (pintype "passive"))
      (node (ref "R48") (pin "1") (pinfunction "1_1") (pintype "passive"))
      (node (ref "R49") (pin "1") (pinfunction "1_1") (pintype "passive"))
      (node (ref "R50") (pin "2") (pinfunction "2_2") (pintype "passive"))
      (node (ref "RN1") (pin "1") (pinfunction "1_1") (pintype "passive"))
      (node (ref "RN3") (pin "1") (pinfunction "1_1") (pintype "passive"))
      (node (ref "SJ5") (pin "P$1") (pinfunction "1_P$1") (pintype "passive"))
      (node (ref "U3") (pin "16") (pinfunction "VCC_16") (pintype "power_in"))
      (node (ref "U3") (pin "9") (pinfunction "CLR_9") (pintype "input"))
      (node (ref "U4") (pin "1") (pinfunction "SER_1") (pintype "input"))
      (node (ref "U4") (pin "16") (pinfunction "VCC_16") (pintype "power_in"))
      (node (ref "U4") (pin "9") (pinfunction "CLR_9") (pintype "input"))
    )
    (net (code "2") (name "+5V") (class "Default")
      (node (ref "C1") (pin "1") (pinfunction "1_1") (pintype "passive"))
      (node (ref "C11") (pin "1") (pinfunction "1_1") (pintype "passive"))
      (node (ref "C2") (pin "1") (pinfunction "1_1") (pintype "passive"))
      (node (ref "C3") (pin "1") (pinfunction "1_1") (pintype "passive"))
      (node (ref "G1") (pin "5V2") (pinfunction "5V2_5V2") (pintype "power_in"))
      (node (ref "IC2") (pin "3") (pinfunction "VDD_3") (pintype "power_in"))
      (node (ref "JP1") (pin "3") (pinfunction "3_3") (pintype "passive"))
      (node (ref "JP1") (pin "4") (pinfunction "4_4") (pintype "passive"))
      (node (ref "JP10") (pin "6") (pinfunction "6_6") (pintype "passive"))
      (node (ref "JP2") (pin "3") (pinfunction "3_3") (pintype "passive"))
      (node (ref "JP2") (pin "4") (pinfunction "4_4") (pintype "passive"))
      (node (ref "JP3") (pin "3") (pinfunction "3_3") (pintype "passive"))
      (node (ref "JP3") (pin "4") (pinfunction "4_4") (pintype "passive"))
      (node (ref "JP4") (pin "3") (pinfunction "3_3") (pintype "passive"))
      (node (ref "JP4") (pin "4") (pinfunction "4_4") (pintype "passive"))
      (node (ref "JP5") (pin "6") (pinfunction "6_6") (pintype "passive"))
      (node (ref "JP6") (pin "3") (pinfunction "3_3") (pintype "passive"))
      (node (ref "JP8") (pin "6") (pinfunction "6_6") (pintype "passive"))
      (node (ref "JP9") (pin "6") (pinfunction "6_6") (pintype "passive"))
      (node (ref "R1") (pin "1") (pinfunction "1_1") (pintype "passive"))
      (node (ref "R10") (pin "1") (pinfunction "1_1") (pintype "passive"))
      (node (ref "R11") (pin "1") (pinfunction "1_1") (pintype "passive"))
      (node (ref "R12") (pin "1") (pinfunction "1_1") (pintype "passive"))
      (node (ref "R13") (pin "1") (pinfunction "1_1") (pintype "passive"))
      (node (ref "R14") (pin "1") (pinfunction "1_1") (pintype "passive"))
      (node (ref "R15") (pin "1") (pinfunction "1_1") (pintype "passive"))
      (node (ref "R2") (pin "1") (pinfunction "1_1") (pintype "passive"))
      (node (ref "R3") (pin "2") (pinfunction "2_2") (pintype "passive"))
      (node (ref "R4") (pin "2") (pinfunction "2_2") (pintype "passive"))
      (node (ref "R5") (pin "2") (pinfunction "2_2") (pintype "passive"))
      (node (ref "R6") (pin "1") (pinfunction "1_1") (pintype "passive"))
      (node (ref "R7") (pin "1") (pinfunction "1_1") (pintype "passive"))
      (node (ref "R8") (pin "1") (pinfunction "1_1") (pintype "passive"))
      (node (ref "R9") (pin "1") (pinfunction "1_1") (pintype "passive"))
      (node (ref "SJ14") (pin "P$2") (pinfunction "2_P$2") (pintype "passive"))
      (node (ref "SJ15") (pin "P$2") (pinfunction "2_P$2") (pintype "passive"))
      (node (ref "SJ7") (pin "P$2") (pinfunction "2_P$2") (pintype "passive"))
      (node (ref "SJ8") (pin "P$2") (pinfunction "2_P$2") (pintype "passive"))
      (node (ref "U1") (pin "3") (pinfunction "VCC_3") (pintype "power_in"))
      (node (ref "U11") (pin "10") (pinfunction "SCL_10") (pintype "input"))
      (node (ref "U11") (pin "16") (pinfunction "VCC_16") (pintype "power_in"))
      (node (ref "U13") (pin "10") (pinfunction "SCL_10") (pintype "input"))
      (node (ref "U13") (pin "16") (pinfunction "VCC_16") (pintype "power_in"))
      (node (ref "X5") (pin "1") (pinfunction "1_1") (pintype "passive"))
    )
    (net (code "3") (name "+12V") (class "Default")
      (node (ref "C10") (pin "1") (pinfunction "1_1") (pintype "passive"))
      (node (ref "C5") (pin "1") (pinfunction "1_1") (pintype "passive"))
      (node (ref "C9") (pin "1") (pinfunction "1_1") (pintype "passive"))
      (node (ref "D5") (pin "C") (pinfunction "C_C") (pintype "passive"))
      (node (ref "D6") (pin "C") (pinfunction "C_C") (pintype "passive"))
      (node (ref "IC1") (pin "5") (pinfunction "IN_5") (pintype "input"))
      (node (ref "JP5") (pin "7") (pinfunction "7_7") (pintype "passive"))
      (node (ref "JP7") (pin "2") (pinfunction "2_2") (pintype "passive"))
      (node (ref "SJ10") (pin "P$2") (pinfunction "2_P$2") (pintype "passive"))
      (node (ref "SJ16") (pin "P$2") (pinfunction "2_P$2") (pintype "passive"))
      (node (ref "SJ17") (pin "P$2") (pinfunction "2_P$2") (pintype "passive"))
      (node (ref "SJ2") (pin "P$2") (pinfunction "2_P$2") (pintype "passive"))
      (node (ref "SJ9") (pin "P$2") (pinfunction "2_P$2") (pintype "passive"))
      (node (ref "U10") (pin "6") (pinfunction "VDD_6") (pintype "power_in"))
      (node (ref "U2") (pin "1") (pinfunction "VIN_1") (pintype "bidirectional"))
      (node (ref "U5") (pin "6") (pinfunction "VDD_6") (pintype "power_in"))
      (node (ref "U6") (pin "4") (pinfunction "V+_4") (pintype "power_in"))
      (node (ref "U7") (pin "6") (pinfunction "VDD_6") (pintype "power_in"))
      (node (ref "U8") (pin "6") (pinfunction "VDD_6") (pintype "power_in"))
      (node (ref "U9") (pin "4") (pinfunction "V+_4") (pintype "power_in"))
    )
    (net (code "4") (name "/AGND") (class "Default")
      (node (ref "G1") (pin "AGND") (pinfunction "AGND_AGND") (pintype "power_in"))
    )
    (net (code "5") (name "/AVDD") (class "Default")
      (node (ref "G1") (pin "AVDD") (pinfunction "AVDD_AVDD") (pintype "power_in"))
    )
    (net (code "6") (name "/CANH") (class "Default")
      (node (ref "IC2") (pin "7") (pinfunction "CANH_7") (pintype "bidirectional"))
      (node (ref "U1") (pin "7") (pinfunction "CANH_7") (pintype "bidirectional"))
      (node (ref "X1") (pin "1") (pinfunction "1_1") (pintype "passive"))
      (node (ref "X2") (pin "1") (pinfunction "1_1") (pintype "passive"))
    )
    (net (code "7") (name "/CANL") (class "Default")
      (node (ref "IC2") (pin "6") (pinfunction "CANL_6") (pintype "bidirectional"))
      (node (ref "U1") (pin "6") (pinfunction "CANL_6") (pintype "bidirectional"))
      (node (ref "X1") (pin "2") (pinfunction "2_2") (pintype "passive"))
      (node (ref "X2") (pin "2") (pinfunction "2_2") (pintype "passive"))
    )
    (net (code "8") (name "/GND4") (class "Default")
      (node (ref "G1") (pin "GND4") (pinfunction "GND4_GND4") (pintype "power_in"))
    )
    (net (code "9") (name "/PWR_POS") (class "Default")
      (node (ref "R17") (pin "2") (pinfunction "2_2") (pintype "passive"))
      (node (ref "X1") (pin "8") (pinfunction "8_8") (pintype "passive"))
      (node (ref "X2") (pin "8") (pinfunction "8_8") (pintype "passive"))
    )
    (net (code "10") (name "/U5V") (class "Default")
      (node (ref "G1") (pin "U5V") (pinfunction "U5V_U5V") (pintype "power_in"))
    )
    (net (code "11") (name "/VBAT") (class "Default")
      (node (ref "G1") (pin "VBAT") (pinfunction "VBAT_VBAT") (pintype "power_in"))
    )
    (net (code "12") (name "/VDD") (class "Default")
      (node (ref "G1") (pin "VDD") (pinfunction "VDD_VDD") (pintype "power_in"))
    )
    (net (code "13") (name "CANRX") (class "Default")
      (node (ref "G1") (pin "PB8") (pinfunction "PB8_PB8") (pintype "bidirectional"))
      (node (ref "IC2") (pin "4") (pinfunction "RXD_4") (pintype "bidirectional"))
      (node (ref "U1") (pin "4") (pinfunction "RXD_4") (pintype "output"))
    )
    (net (code "14") (name "CANTX") (class "Default")
      (node (ref "G1") (pin "PB9") (pinfunction "PB9_PB9") (pintype "bidirectional"))
      (node (ref "IC2") (pin "1") (pinfunction "TXD_1") (pintype "bidirectional"))
      (node (ref "U1") (pin "1") (pinfunction "TXD_1") (pintype "input"))
    )
    (net (code "15") (name "E_CS") (class "Default")
      (node (ref "G1") (pin "PC10") (pinfunction "PC10_PC10") (pintype "bidirectional"))
      (node (ref "JP5") (pin "4") (pinfunction "4_4") (pintype "passive"))
      (node (ref "R1") (pin "2") (pinfunction "2_2") (pintype "passive"))
    )
    (net (code "16") (name "E_LAT") (class "Default")
      (node (ref "G1") (pin "PC11") (pinfunction "PC11_PC11") (pintype "bidirectional"))
      (node (ref "JP5") (pin "5") (pinfunction "5_5") (pintype "passive"))
      (node (ref "R2") (pin "2") (pinfunction "2_2") (pintype "passive"))
    )
    (net (code "17") (name "GND") (class "Default")
      (node (ref "C1") (pin "2") (pinfunction "2_2") (pintype "passive"))
      (node (ref "C10") (pin "2") (pinfunction "2_2") (pintype "passive"))
      (node (ref "C11") (pin "2") (pinfunction "2_2") (pintype "passive"))
      (node (ref "C2") (pin "2") (pinfunction "2_2") (pintype "passive"))
      (node (ref "C3") (pin "2") (pinfunction "2_2") (pintype "passive"))
      (node (ref "C4") (pin "2") (pinfunction "2_2") (pintype "passive"))
      (node (ref "C5") (pin "2") (pinfunction "2_2") (pintype "passive"))
      (node (ref "C6") (pin "-") (pinfunction "-_-") (pintype "passive"))
      (node (ref "C7") (pin "2") (pinfunction "2_2") (pintype "passive"))
      (node (ref "C8") (pin "2") (pinfunction "2_2") (pintype "passive"))
      (node (ref "C9") (pin "2") (pinfunction "2_2") (pintype "passive"))
      (node (ref "D3") (pin "A") (pinfunction "A_A") (pintype "passive"))
      (node (ref "D4") (pin "A") (pinfunction "A_A") (pintype "passive"))
      (node (ref "G1") (pin "GND3") (pinfunction "GND3_GND3") (pintype "power_in"))
      (node (ref "G1") (pin "GND5") (pinfunction "GND5_GND5") (pintype "power_in"))
      (node (ref "G1") (pin "GND6") (pinfunction "GND6_GND6") (pintype "power_in"))
      (node (ref "G1") (pin "GND7") (pinfunction "GND7_GND7") (pintype "power_in"))
      (node (ref "G1") (pin "GND8") (pinfunction "GND8_GND8") (pintype "power_in"))
      (node (ref "IC1") (pin "2") (pinfunction "GNDSIG_2") (pintype "input"))
      (node (ref "IC1") (pin "3") (pinfunction "~{ON/OFF}_3") (pintype "input"))
      (node (ref "IC1") (pin "4") (pinfunction "GND_4") (pintype "power_in"))
      (node (ref "IC2") (pin "2") (pinfunction "VSS_2") (pintype "power_in"))
      (node (ref "J1") (pin "2") (pinfunction "2_2") (pintype "passive"))
      (node (ref "J1") (pin "3") (pinfunction "3_3") (pintype "passive"))
      (node (ref "JP1") (pin "5") (pinfunction "5_5") (pintype "passive"))
      (node (ref "JP1") (pin "6") (pinfunction "6_6") (pintype "passive"))
      (node (ref "JP10") (pin "5") (pinfunction "5_5") (pintype "passive"))
      (node (ref "JP2") (pin "5") (pinfunction "5_5") (pintype "passive"))
      (node (ref "JP2") (pin "6") (pinfunction "6_6") (pintype "passive"))
      (node (ref "JP3") (pin "5") (pinfunction "5_5") (pintype "passive"))
      (node (ref "JP3") (pin "6") (pinfunction "6_6") (pintype "passive"))
      (node (ref "JP4") (pin "5") (pinfunction "5_5") (pintype "passive"))
      (node (ref "JP4") (pin "6") (pinfunction "6_6") (pintype "passive"))
      (node (ref "JP5") (pin "8") (pinfunction "8_8") (pintype "passive"))
      (node (ref "JP6") (pin "4") (pinfunction "4_4") (pintype "passive"))
      (node (ref "JP8") (pin "5") (pinfunction "5_5") (pintype "passive"))
      (node (ref "JP9") (pin "5") (pinfunction "5_5") (pintype "passive"))
      (node (ref "Q1") (pin "2") (pinfunction "S_2") (pintype "passive"))
      (node (ref "Q10") (pin "2") (pinfunction "S_2") (pintype "passive"))
      (node (ref "Q11") (pin "2") (pinfunction "S_2") (pintype "passive"))
      (node (ref "Q12") (pin "2") (pinfunction "S_2") (pintype "passive"))
      (node (ref "Q13") (pin "2") (pinfunction "S_2") (pintype "passive"))
      (node (ref "Q14") (pin "2") (pinfunction "S_2") (pintype "passive"))
      (node (ref "Q15") (pin "2") (pinfunction "S_2") (pintype "passive"))
      (node (ref "Q16") (pin "2") (pinfunction "S_2") (pintype "passive"))
      (node (ref "Q2") (pin "2") (pinfunction "S_2") (pintype "passive"))
      (node (ref "Q3") (pin "2") (pinfunction "S_2") (pintype "passive"))
      (node (ref "Q4") (pin "2") (pinfunction "S_2") (pintype "passive"))
      (node (ref "Q5") (pin "2") (pinfunction "S_2") (pintype "passive"))
      (node (ref "Q6") (pin "2") (pinfunction "S_2") (pintype "passive"))
      (node (ref "Q7") (pin "2") (pinfunction "S_2") (pintype "passive"))
      (node (ref "Q8") (pin "2") (pinfunction "S_2") (pintype "passive"))
      (node (ref "Q9") (pin "2") (pinfunction "S_2") (pintype "passive"))
      (node (ref "R16") (pin "2") (pinfunction "2_2") (pintype "passive"))
      (node (ref "R51") (pin "1") (pinfunction "1_1") (pintype "passive"))
      (node (ref "SJ11") (pin "2") (pinfunction "2_2") (pintype "passive"))
      (node (ref "SJ12") (pin "P$2") (pinfunction "2_P$2") (pintype "passive"))
      (node (ref "SJ18") (pin "2") (pinfunction "2_2") (pintype "passive"))
      (node (ref "SJ19") (pin "P$2") (pinfunction "2_P$2") (pintype "passive"))
      (node (ref "U1") (pin "2") (pinfunction "GND_2") (pintype "power_in"))
      (node (ref "U10") (pin "3") (pinfunction "VSS_3") (pintype "power_in"))
      (node (ref "U11") (pin "13") (pinfunction "G_13") (pintype "input"))
      (node (ref "U11") (pin "8") (pinfunction "GND_8") (pintype "power_in"))
      (node (ref "U13") (pin "13") (pinfunction "G_13") (pintype "input"))
      (node (ref "U13") (pin "8") (pinfunction "GND_8") (pintype "power_in"))
      (node (ref "U2") (pin "4") (pinfunction "SD_4") (pintype "bidirectional"))
      (node (ref "U2") (pin "5") (pinfunction "GND1_5") (pintype "power_in"))
      (node (ref "U2") (pin "6") (pinfunction "GND2_6") (pintype "power_in"))
      (node (ref "U2") (pin "7") (pinfunction "GND3_7") (pintype "power_in"))
      (node (ref "U2") (pin "8") (pinfunction "GND4_8") (pintype "power_in"))
      (node (ref "U3") (pin "6") (pinfunction "INH_6") (pintype "input"))
      (node (ref "U3") (pin "8") (pinfunction "GND_8") (pintype "power_in"))
      (node (ref "U4") (pin "6") (pinfunction "INH_6") (pintype "input"))
      (node (ref "U4") (pin "8") (pinfunction "GND_8") (pintype "power_in"))
      (node (ref "U5") (pin "3") (pinfunction "VSS_3") (pintype "power_in"))
      (node (ref "U6") (pin "11") (pinfunction "V-_11") (pintype "power_in"))
      (node (ref "U7") (pin "3") (pinfunction "VSS_3") (pintype "power_in"))
      (node (ref "U8") (pin "3") (pinfunction "VSS_3") (pintype "power_in"))
      (node (ref "U9") (pin "11") (pinfunction "V-_11") (pintype "power_in"))
      (node (ref "X1") (pin "3") (pinfunction "3_3") (pintype "passive"))
      (node (ref "X1") (pin "6") (pinfunction "6_6") (pintype "passive"))
      (node (ref "X1") (pin "7") (pinfunction "7_7") (pintype "passive"))
      (node (ref "X2") (pin "3") (pinfunction "3_3") (pintype "passive"))
      (node (ref "X2") (pin "6") (pinfunction "6_6") (pintype "passive"))
      (node (ref "X2") (pin "7") (pinfunction "7_7") (pintype "passive"))
      (node (ref "X5") (pin "2") (pinfunction "2_2") (pintype "passive"))
      (node (ref "X9") (pin "2") (pinfunction "2_2") (pintype "passive"))
    )
    (net (code "18") (name "I2CSCL") (class "Default")
      (node (ref "G1") (pin "PB6") (pinfunction "PB6_PB6") (pintype "bidirectional"))
      (node (ref "JP6") (pin "1") (pinfunction "1_1") (pintype "passive"))
      (node (ref "R15") (pin "2") (pinfunction "2_2") (pintype "passive"))
    )
    (net (code "19") (name "I2CSDA") (class "Default")
      (node (ref "G1") (pin "PB7") (pinfunction "PB7_PB7") (pintype "bidirectional"))
      (node (ref "JP6") (pin "2") (pinfunction "2_2") (pintype "passive"))
      (node (ref "R14") (pin "2") (pinfunction "2_2") (pintype "passive"))
    )
    (net (code "20") (name "ILAT") (class "Default")
      (node (ref "G1") (pin "PA6") (pinfunction "PA6_PA6") (pintype "bidirectional"))
      (node (ref "U3") (pin "15") (pinfunction "SH/~{LD}_15") (pintype "input"))
      (node (ref "U4") (pin "15") (pinfunction "SH/~{LD}_15") (pintype "input"))
    )
    (net (code "21") (name "MISO") (class "Default")
      (node (ref "G1") (pin "PB4") (pinfunction "PB4_PB4") (pintype "bidirectional"))
      (node (ref "JP5") (pin "1") (pinfunction "1_1") (pintype "passive"))
    )
    (net (code "22") (name "MISO2") (class "Default")
      (node (ref "G1") (pin "PC2") (pinfunction "PC2_PC2") (pintype "bidirectional"))
      (node (ref "SJ1") (pin "P$2") (pinfunction "2_P$2") (pintype "passive"))
      (node (ref "SJ6") (pin "P$2") (pinfunction "2_P$2") (pintype "passive"))
      (node (ref "U3") (pin "13") (pinfunction "QH_13") (pintype "output"))
    )
    (net (code "23") (name "MOSI") (class "Default")
      (node (ref "G1") (pin "PB5") (pinfunction "PB5_PB5") (pintype "bidirectional"))
      (node (ref "R4") (pin "1") (pinfunction "1_1") (pintype "passive"))
      (node (ref "SJ13") (pin "P$2") (pinfunction "2_P$2") (pintype "passive"))
      (node (ref "SJ3") (pin "1") (pinfunction "1_1") (pintype "passive"))
      (node (ref "U13") (pin "14") (pinfunction "SER_14") (pintype "input"))
    )
    (net (code "24") (name "Net-(D1-PadA)") (class "Default")
      (node (ref "D1") (pin "A") (pinfunction "A_A") (pintype "passive"))
      (node (ref "D2") (pin "A") (pinfunction "A_A") (pintype "passive"))
      (node (ref "JP7") (pin "4") (pinfunction "4_4") (pintype "passive"))
    )
    (net (code "25") (name "Net-(D1-PadC)") (class "Default")
      (node (ref "D1") (pin "C") (pinfunction "C_C") (pintype "passive"))
      (node (ref "D2") (pin "C") (pinfunction "C_C") (pintype "passive"))
      (node (ref "JP7") (pin "1") (pinfunction "1_1") (pintype "passive"))
    )
    (net (code "26") (name "Net-(D5-PadA)") (class "Default")
      (node (ref "D5") (pin "A") (pinfunction "A_A") (pintype "passive"))
      (node (ref "D6") (pin "A") (pinfunction "A_A") (pintype "passive"))
      (node (ref "J1") (pin "1") (pinfunction "1_1") (pintype "passive"))
      (node (ref "X9") (pin "1") (pinfunction "1_1") (pintype "passive"))
    )
    (net (code "27") (name "Net-(IC1-OUT)") (class "Default")
      (node (ref "D3") (pin "C") (pinfunction "C_C") (pintype "passive"))
      (node (ref "D4") (pin "C") (pinfunction "C_C") (pintype "passive"))
      (node (ref "IC1") (pin "7") (pinfunction "OUT_7") (pintype "passive"))
      (node (ref "L1") (pin "2") (pinfunction "2_2") (pintype "passive"))
      (node (ref "U2") (pin "2") (pinfunction "VOUT_2") (pintype "bidirectional"))
    )
    (net (code "28") (name "Net-(IC2-RS)") (class "Default")
      (node (ref "IC2") (pin "8") (pinfunction "RS_8") (pintype "bidirectional"))
      (node (ref "R16") (pin "1") (pinfunction "1_1") (pintype "passive"))
      (node (ref "U1") (pin "8") (pinfunction "RS_8") (pintype "input"))
    )
    (net (code "29") (name "Net-(IC2-VREF)") (class "Default")
      (node (ref "IC2") (pin "5") (pinfunction "VREF_5") (pintype "bidirectional"))
      (node (ref "SJ5") (pin "P$2") (pinfunction "2_P$2") (pintype "passive"))
      (node (ref "U1") (pin "5") (pinfunction "VREF_5") (pintype "output"))
    )
    (net (code "30") (name "Net-(JP7-Pad3)") (class "Default")
      (node (ref "JP7") (pin "3") (pinfunction "3_3") (pintype "passive"))
      (node (ref "R17") (pin "1") (pinfunction "1_1") (pintype "passive"))
    )
    (net (code "31") (name "Net-(JP8-Pad1)") (class "Default")
      (node (ref "JP8") (pin "1") (pinfunction "1_1") (pintype "passive"))
      (node (ref "R25") (pin "2") (pinfunction "2_2") (pintype "passive"))
      (node (ref "R26") (pin "2") (pinfunction "2_2") (pintype "passive"))
      (node (ref "RN1") (pin "9") (pinfunction "9_9") (pintype "passive"))
      (node (ref "RN2") (pin "1") (pinfunction "1_1") (pintype "passive"))
      (node (ref "X3") (pin "1") (pinfunction "1_1") (pintype "passive"))
    )
    (net (code "32") (name "Net-(JP9-Pad1)") (class "Default")
      (node (ref "JP9") (pin "1") (pinfunction "1_1") (pintype "passive"))
      (node (ref "R41") (pin "2") (pinfunction "2_2") (pintype "passive"))
      (node (ref "R42") (pin "2") (pinfunction "2_2") (pintype "passive"))
      (node (ref "RN3") (pin "9") (pinfunction "9_9") (pintype "passive"))
      (node (ref "RN4") (pin "1") (pinfunction "1_1") (pintype "passive"))
      (node (ref "X4") (pin "1") (pinfunction "1_1") (pintype "passive"))
    )
    (net (code "33") (name "Net-(Q1-D)") (class "Default")
      (node (ref "Q1") (pin "3") (pinfunction "D_3") (pintype "passive"))
      (node (ref "U12") (pin "11") (pinfunction "O8_11") (pintype "open_collector"))
      (node (ref "X7") (pin "8") (pinfunction "8_8") (pintype "passive"))
    )
    (net (code "34") (name "Net-(Q1-G)") (class "Default")
      (node (ref "Q1") (pin "1") (pinfunction "G_1") (pintype "passive"))
      (node (ref "R52") (pin "2") (pinfunction "2_2") (pintype "passive"))
    )
    (net (code "35") (name "Net-(Q2-D)") (class "Default")
      (node (ref "Q2") (pin "3") (pinfunction "D_3") (pintype "passive"))
      (node (ref "U12") (pin "12") (pinfunction "O7_12") (pintype "open_collector"))
      (node (ref "X7") (pin "7") (pinfunction "7_7") (pintype "passive"))
    )
    (net (code "36") (name "Net-(Q2-G)") (class "Default")
      (node (ref "Q2") (pin "1") (pinfunction "G_1") (pintype "passive"))
      (node (ref "R53") (pin "2") (pinfunction "2_2") (pintype "passive"))
    )
    (net (code "37") (name "Net-(Q3-D)") (class "Default")
      (node (ref "Q3") (pin "3") (pinfunction "D_3") (pintype "passive"))
      (node (ref "U12") (pin "13") (pinfunction "O6_13") (pintype "open_collector"))
      (node (ref "X7") (pin "6") (pinfunction "6_6") (pintype "passive"))
    )
    (net (code "38") (name "Net-(Q3-G)") (class "Default")
      (node (ref "Q3") (pin "1") (pinfunction "G_1") (pintype "passive"))
      (node (ref "R54") (pin "2") (pinfunction "2_2") (pintype "passive"))
    )
    (net (code "39") (name "Net-(Q4-D)") (class "Default")
      (node (ref "Q4") (pin "3") (pinfunction "D_3") (pintype "passive"))
      (node (ref "U12") (pin "14") (pinfunction "O5_14") (pintype "open_collector"))
      (node (ref "X7") (pin "5") (pinfunction "5_5") (pintype "passive"))
    )
    (net (code "40") (name "Net-(Q4-G)") (class "Default")
      (node (ref "Q4") (pin "1") (pinfunction "G_1") (pintype "passive"))
      (node (ref "R55") (pin "2") (pinfunction "2_2") (pintype "passive"))
    )
    (net (code "41") (name "Net-(Q5-D)") (class "Default")
      (node (ref "Q5") (pin "3") (pinfunction "D_3") (pintype "passive"))
      (node (ref "U12") (pin "15") (pinfunction "O4_15") (pintype "open_collector"))
      (node (ref "X7") (pin "4") (pinfunction "4_4") (pintype "passive"))
    )
    (net (code "42") (name "Net-(Q5-G)") (class "Default")
      (node (ref "Q5") (pin "1") (pinfunction "G_1") (pintype "passive"))
      (node (ref "R56") (pin "2") (pinfunction "2_2") (pintype "passive"))
    )
    (net (code "43") (name "Net-(Q6-D)") (class "Default")
      (node (ref "Q6") (pin "3") (pinfunction "D_3") (pintype "passive"))
      (node (ref "U12") (pin "16") (pinfunction "O3_16") (pintype "open_collector"))
      (node (ref "X7") (pin "3") (pinfunction "3_3") (pintype "passive"))
    )
    (net (code "44") (name "Net-(Q6-G)") (class "Default")
      (node (ref "Q6") (pin "1") (pinfunction "G_1") (pintype "passive"))
      (node (ref "R57") (pin "2") (pinfunction "2_2") (pintype "passive"))
    )
    (net (code "45") (name "Net-(Q7-D)") (class "Default")
      (node (ref "Q7") (pin "3") (pinfunction "D_3") (pintype "passive"))
      (node (ref "U12") (pin "17") (pinfunction "O2_17") (pintype "open_collector"))
      (node (ref "X7") (pin "2") (pinfunction "2_2") (pintype "passive"))
    )
    (net (code "46") (name "Net-(Q7-G)") (class "Default")
      (node (ref "Q7") (pin "1") (pinfunction "G_1") (pintype "passive"))
      (node (ref "R58") (pin "2") (pinfunction "2_2") (pintype "passive"))
    )
    (net (code "47") (name "Net-(Q8-D)") (class "Default")
      (node (ref "Q8") (pin "3") (pinfunction "D_3") (pintype "passive"))
      (node (ref "U12") (pin "18") (pinfunction "O1_18") (pintype "open_collector"))
      (node (ref "X7") (pin "1") (pinfunction "1_1") (pintype "passive"))
    )
    (net (code "48") (name "Net-(Q8-G)") (class "Default")
      (node (ref "Q8") (pin "1") (pinfunction "G_1") (pintype "passive"))
      (node (ref "R59") (pin "2") (pinfunction "2_2") (pintype "passive"))
    )
    (net (code "49") (name "Net-(Q9-D)") (class "Default")
      (node (ref "Q9") (pin "3") (pinfunction "D_3") (pintype "passive"))
      (node (ref "U14") (pin "11") (pinfunction "O8_11") (pintype "open_collector"))
      (node (ref "X8") (pin "8") (pinfunction "8_8") (pintype "passive"))
    )
    (net (code "50") (name "Net-(Q9-G)") (class "Default")
      (node (ref "Q9") (pin "1") (pinfunction "G_1") (pintype "passive"))
      (node (ref "R60") (pin "2") (pinfunction "2_2") (pintype "passive"))
    )
    (net (code "51") (name "Net-(Q10-D)") (class "Default")
      (node (ref "Q10") (pin "3") (pinfunction "D_3") (pintype "passive"))
      (node (ref "U14") (pin "12") (pinfunction "O7_12") (pintype "open_collector"))
      (node (ref "X8") (pin "7") (pinfunction "7_7") (pintype "passive"))
    )
    (net (code "52") (name "Net-(Q10-G)") (class "Default")
      (node (ref "Q10") (pin "1") (pinfunction "G_1") (pintype "passive"))
      (node (ref "R61") (pin "2") (pinfunction "2_2") (pintype "passive"))
    )
    (net (code "53") (name "Net-(Q11-D)") (class "Default")
      (node (ref "Q11") (pin "3") (pinfunction "D_3") (pintype "passive"))
      (node (ref "U14") (pin "13") (pinfunction "O6_13") (pintype "open_collector"))
      (node (ref "X8") (pin "6") (pinfunction "6_6") (pintype "passive"))
    )
    (net (code "54") (name "Net-(Q11-G)") (class "Default")
      (node (ref "Q11") (pin "1") (pinfunction "G_1") (pintype "passive"))
      (node (ref "R62") (pin "2") (pinfunction "2_2") (pintype "passive"))
    )
    (net (code "55") (name "Net-(Q12-D)") (class "Default")
      (node (ref "Q12") (pin "3") (pinfunction "D_3") (pintype "passive"))
      (node (ref "U14") (pin "14") (pinfunction "O5_14") (pintype "open_collector"))
      (node (ref "X8") (pin "5") (pinfunction "5_5") (pintype "passive"))
    )
    (net (code "56") (name "Net-(Q12-G)") (class "Default")
      (node (ref "Q12") (pin "1") (pinfunction "G_1") (pintype "passive"))
      (node (ref "R63") (pin "2") (pinfunction "2_2") (pintype "passive"))
    )
    (net (code "57") (name "Net-(Q13-D)") (class "Default")
      (node (ref "Q13") (pin "3") (pinfunction "D_3") (pintype "passive"))
      (node (ref "U14") (pin "15") (pinfunction "O4_15") (pintype "open_collector"))
      (node (ref "X8") (pin "4") (pinfunction "4_4") (pintype "passive"))
    )
    (net (code "58") (name "Net-(Q13-G)") (class "Default")
      (node (ref "Q13") (pin "1") (pinfunction "G_1") (pintype "passive"))
      (node (ref "R64") (pin "2") (pinfunction "2_2") (pintype "passive"))
    )
    (net (code "59") (name "Net-(Q14-D)") (class "Default")
      (node (ref "Q14") (pin "3") (pinfunction "D_3") (pintype "passive"))
      (node (ref "U14") (pin "16") (pinfunction "O3_16") (pintype "open_collector"))
      (node (ref "X8") (pin "3") (pinfunction "3_3") (pintype "passive"))
    )
    (net (code "60") (name "Net-(Q14-G)") (class "Default")
      (node (ref "Q14") (pin "1") (pinfunction "G_1") (pintype "passive"))
      (node (ref "R65") (pin "2") (pinfunction "2_2") (pintype "passive"))
    )
    (net (code "61") (name "Net-(Q15-D)") (class "Default")
      (node (ref "Q15") (pin "3") (pinfunction "D_3") (pintype "passive"))
      (node (ref "U14") (pin "17") (pinfunction "O2_17") (pintype "open_collector"))
      (node (ref "X8") (pin "2") (pinfunction "2_2") (pintype "passive"))
    )
    (net (code "62") (name "Net-(Q15-G)") (class "Default")
      (node (ref "Q15") (pin "1") (pinfunction "G_1") (pintype "passive"))
      (node (ref "R66") (pin "2") (pinfunction "2_2") (pintype "passive"))
    )
    (net (code "63") (name "Net-(Q16-D)") (class "Default")
      (node (ref "Q16") (pin "3") (pinfunction "D_3") (pintype "passive"))
      (node (ref "U14") (pin "18") (pinfunction "O1_18") (pintype "open_collector"))
      (node (ref "X8") (pin "1") (pinfunction "1_1") (pintype "passive"))
    )
    (net (code "64") (name "Net-(Q16-G)") (class "Default")
      (node (ref "Q16") (pin "1") (pinfunction "G_1") (pintype "passive"))
      (node (ref "R67") (pin "2") (pinfunction "2_2") (pintype "passive"))
    )
    (net (code "65") (name "Net-(RN2A-2)") (class "Default")
      (node (ref "R25") (pin "1") (pinfunction "1_1") (pintype "passive"))
      (node (ref "RN2") (pin "16") (pinfunction "2_16") (pintype "passive"))
      (node (ref "U3") (pin "14") (pinfunction "H_14") (pintype "input"))
    )
    (net (code "66") (name "Net-(RN2B-1)") (class "Default")
      (node (ref "JP8") (pin "2") (pinfunction "2_2") (pintype "passive"))
      (node (ref "R24") (pin "2") (pinfunction "2_2") (pintype "passive"))
      (node (ref "R27") (pin "2") (pinfunction "2_2") (pintype "passive"))
      (node (ref "RN1") (pin "8") (pinfunction "8_8") (pintype "passive"))
      (node (ref "RN2") (pin "2") (pinfunction "1_2") (pintype "passive"))
      (node (ref "X3") (pin "2") (pinfunction "2_2") (pintype "passive"))
    )
    (net (code "67") (name "Net-(RN2B-2)") (class "Default")
      (node (ref "R24") (pin "1") (pinfunction "1_1") (pintype "passive"))
      (node (ref "RN2") (pin "15") (pinfunction "2_15") (pintype "passive"))
      (node (ref "U3") (pin "12") (pinfunction "G_12") (pintype "input"))
    )
    (net (code "68") (name "Net-(RN2C-1)") (class "Default")
      (node (ref "JP8") (pin "3") (pinfunction "3_3") (pintype "passive"))
      (node (ref "R23") (pin "2") (pinfunction "2_2") (pintype "passive"))
      (node (ref "R28") (pin "2") (pinfunction "2_2") (pintype "passive"))
      (node (ref "RN1") (pin "7") (pinfunction "7_7") (pintype "passive"))
      (node (ref "RN2") (pin "3") (pinfunction "1_3") (pintype "passive"))
      (node (ref "X3") (pin "3") (pinfunction "3_3") (pintype "passive"))
    )
    (net (code "69") (name "Net-(RN2C-2)") (class "Default")
      (node (ref "R23") (pin "1") (pinfunction "1_1") (pintype "passive"))
      (node (ref "RN2") (pin "14") (pinfunction "2_14") (pintype "passive"))
      (node (ref "U3") (pin "11") (pinfunction "F_11") (pintype "input"))
    )
    (net (code "70") (name "Net-(RN2D-1)") (class "Default")
      (node (ref "JP8") (pin "4") (pinfunction "4_4") (pintype "passive"))
      (node (ref "R22") (pin "2") (pinfunction "2_2") (pintype "passive"))
      (node (ref "R29") (pin "2") (pinfunction "2_2") (pintype "passive"))
      (node (ref "RN1") (pin "6") (pinfunction "6_6") (pintype "passive"))
      (node (ref "RN2") (pin "4") (pinfunction "1_4") (pintype "passive"))
      (node (ref "X3") (pin "4") (pinfunction "4_4") (pintype "passive"))
    )
    (net (code "71") (name "Net-(RN2D-2)") (class "Default")
      (node (ref "R22") (pin "1") (pinfunction "1_1") (pintype "passive"))
      (node (ref "RN2") (pin "13") (pinfunction "2_13") (pintype "passive"))
      (node (ref "U3") (pin "10") (pinfunction "E_10") (pintype "input"))
    )
    (net (code "72") (name "Net-(RN2E-1)") (class "Default")
      (node (ref "JP8") (pin "7") (pinfunction "7_7") (pintype "passive"))
      (node (ref "R21") (pin "2") (pinfunction "2_2") (pintype "passive"))
      (node (ref "R30") (pin "2") (pinfunction "2_2") (pintype "passive"))
      (node (ref "RN1") (pin "5") (pinfunction "5_5") (pintype "passive"))
      (node (ref "RN2") (pin "5") (pinfunction "1_5") (pintype "passive"))
      (node (ref "X3") (pin "5") (pinfunction "5_5") (pintype "passive"))
    )
    (net (code "73") (name "Net-(RN2E-2)") (class "Default")
      (node (ref "R21") (pin "1") (pinfunction "1_1") (pintype "passive"))
      (node (ref "RN2") (pin "12") (pinfunction "2_12") (pintype "passive"))
      (node (ref "U3") (pin "5") (pinfunction "D_5") (pintype "input"))
    )
    (net (code "74") (name "Net-(RN2F-1)") (class "Default")
      (node (ref "JP8") (pin "8") (pinfunction "8_8") (pintype "passive"))
      (node (ref "R20") (pin "2") (pinfunction "2_2") (pintype "passive"))
      (node (ref "R31") (pin "2") (pinfunction "2_2") (pintype "passive"))
      (node (ref "RN1") (pin "4") (pinfunction "4_4") (pintype "passive"))
      (node (ref "RN2") (pin "6") (pinfunction "1_6") (pintype "passive"))
      (node (ref "X3") (pin "6") (pinfunction "6_6") (pintype "passive"))
    )
    (net (code "75") (name "Net-(RN2F-2)") (class "Default")
      (node (ref "R20") (pin "1") (pinfunction "1_1") (pintype "passive"))
      (node (ref "RN2") (pin "11") (pinfunction "2_11") (pintype "passive"))
      (node (ref "U3") (pin "4") (pinfunction "C_4") (pintype "input"))
    )
    (net (code "76") (name "Net-(RN2G-1)") (class "Default")
      (node (ref "JP8") (pin "9") (pinfunction "9_9") (pintype "passive"))
      (node (ref "R19") (pin "2") (pinfunction "2_2") (pintype "passive"))
      (node (ref "R32") (pin "2") (pinfunction "2_2") (pintype "passive"))
      (node (ref "RN1") (pin "3") (pinfunction "3_3") (pintype "passive"))
      (node (ref "RN2") (pin "7") (pinfunction "1_7") (pintype "passive"))
      (node (ref "X3") (pin "7") (pinfunction "7_7") (pintype "passive"))
    )
    (net (code "77") (name "Net-(RN2G-2)") (class "Default")
      (node (ref "R19") (pin "1") (pinfunction "1_1") (pintype "passive"))
      (node (ref "RN2") (pin "10") (pinfunction "2_10") (pintype "passive"))
      (node (ref "U3") (pin "3") (pinfunction "B_3") (pintype "input"))
    )
    (net (code "78") (name "Net-(RN2H-1)") (class "Default")
      (node (ref "JP8") (pin "10") (pinfunction "10_10") (pintype "passive"))
      (node (ref "R18") (pin "2") (pinfunction "2_2") (pintype "passive"))
      (node (ref "R33") (pin "2") (pinfunction "2_2") (pintype "passive"))
      (node (ref "RN1") (pin "2") (pinfunction "2_2") (pintype "passive"))
      (node (ref "RN2") (pin "8") (pinfunction "1_8") (pintype "passive"))
      (node (ref "X3") (pin "8") (pinfunction "8_8") (pintype "passive"))
    )
    (net (code "79") (name "Net-(RN2H-2)") (class "Default")
      (node (ref "R18") (pin "1") (pinfunction "1_1") (pintype "passive"))
      (node (ref "RN2") (pin "9") (pinfunction "2_9") (pintype "passive"))
      (node (ref "U3") (pin "2") (pinfunction "A_2") (pintype "input"))
    )
    (net (code "80") (name "Net-(RN4A-2)") (class "Default")
      (node (ref "R41") (pin "1") (pinfunction "1_1") (pintype "passive"))
      (node (ref "RN4") (pin "16") (pinfunction "2_16") (pintype "passive"))
      (node (ref "U4") (pin "14") (pinfunction "H_14") (pintype "input"))
    )
    (net (code "81") (name "Net-(RN4B-1)") (class "Default")
      (node (ref "JP9") (pin "2") (pinfunction "2_2") (pintype "passive"))
      (node (ref "R40") (pin "2") (pinfunction "2_2") (pintype "passive"))
      (node (ref "R43") (pin "2") (pinfunction "2_2") (pintype "passive"))
      (node (ref "RN3") (pin "8") (pinfunction "8_8") (pintype "passive"))
      (node (ref "RN4") (pin "2") (pinfunction "1_2") (pintype "passive"))
      (node (ref "X4") (pin "2") (pinfunction "2_2") (pintype "passive"))
    )
    (net (code "82") (name "Net-(RN4B-2)") (class "Default")
      (node (ref "R40") (pin "1") (pinfunction "1_1") (pintype "passive"))
      (node (ref "RN4") (pin "15") (pinfunction "2_15") (pintype "passive"))
      (node (ref "U4") (pin "12") (pinfunction "G_12") (pintype "input"))
    )
    (net (code "83") (name "Net-(RN4C-1)") (class "Default")
      (node (ref "JP9") (pin "3") (pinfunction "3_3") (pintype "passive"))
      (node (ref "R39") (pin "2") (pinfunction "2_2") (pintype "passive"))
      (node (ref "R44") (pin "2") (pinfunction "2_2") (pintype "passive"))
      (node (ref "RN3") (pin "7") (pinfunction "7_7") (pintype "passive"))
      (node (ref "RN4") (pin "3") (pinfunction "1_3") (pintype "passive"))
      (node (ref "X4") (pin "3") (pinfunction "3_3") (pintype "passive"))
    )
    (net (code "84") (name "Net-(RN4C-2)") (class "Default")
      (node (ref "R39") (pin "1") (pinfunction "1_1") (pintype "passive"))
      (node (ref "RN4") (pin "14") (pinfunction "2_14") (pintype "passive"))
      (node (ref "U4") (pin "11") (pinfunction "F_11") (pintype "input"))
    )
    (net (code "85") (name "Net-(RN4D-1)") (class "Default")
      (node (ref "JP9") (pin "4") (pinfunction "4_4") (pintype "passive"))
      (node (ref "R38") (pin "2") (pinfunction "2_2") (pintype "passive"))
      (node (ref "R45") (pin "2") (pinfunction "2_2") (pintype "passive"))
      (node (ref "RN3") (pin "6") (pinfunction "6_6") (pintype "passive"))
      (node (ref "RN4") (pin "4") (pinfunction "1_4") (pintype "passive"))
      (node (ref "X4") (pin "4") (pinfunction "4_4") (pintype "passive"))
    )
    (net (code "86") (name "Net-(RN4D-2)") (class "Default")
      (node (ref "R38") (pin "1") (pinfunction "1_1") (pintype "passive"))
      (node (ref "RN4") (pin "13") (pinfunction "2_13") (pintype "passive"))
      (node (ref "U4") (pin "10") (pinfunction "E_10") (pintype "input"))
    )
    (net (code "87") (name "Net-(RN4E-1)") (class "Default")
      (node (ref "JP9") (pin "7") (pinfunction "7_7") (pintype "passive"))
      (node (ref "R37") (pin "2") (pinfunction "2_2") (pintype "passive"))
      (node (ref "R46") (pin "2") (pinfunction "2_2") (pintype "passive"))
      (node (ref "RN3") (pin "5") (pinfunction "5_5") (pintype "passive"))
      (node (ref "RN4") (pin "5") (pinfunction "1_5") (pintype "passive"))
      (node (ref "X4") (pin "5") (pinfunction "5_5") (pintype "passive"))
    )
    (net (code "88") (name "Net-(RN4E-2)") (class "Default")
      (node (ref "R37") (pin "1") (pinfunction "1_1") (pintype "passive"))
      (node (ref "RN4") (pin "12") (pinfunction "2_12") (pintype "passive"))
      (node (ref "U4") (pin "5") (pinfunction "D_5") (pintype "input"))
    )
    (net (code "89") (name "Net-(RN4F-1)") (class "Default")
      (node (ref "JP9") (pin "8") (pinfunction "8_8") (pintype "passive"))
      (node (ref "R36") (pin "2") (pinfunction "2_2") (pintype "passive"))
      (node (ref "R47") (pin "2") (pinfunction "2_2") (pintype "passive"))
      (node (ref "RN3") (pin "4") (pinfunction "4_4") (pintype "passive"))
      (node (ref "RN4") (pin "6") (pinfunction "1_6") (pintype "passive"))
      (node (ref "X4") (pin "6") (pinfunction "6_6") (pintype "passive"))
    )
    (net (code "90") (name "Net-(RN4F-2)") (class "Default")
      (node (ref "R36") (pin "1") (pinfunction "1_1") (pintype "passive"))
      (node (ref "RN4") (pin "11") (pinfunction "2_11") (pintype "passive"))
      (node (ref "U4") (pin "4") (pinfunction "C_4") (pintype "input"))
    )
    (net (code "91") (name "Net-(RN4G-1)") (class "Default")
      (node (ref "JP9") (pin "9") (pinfunction "9_9") (pintype "passive"))
      (node (ref "R35") (pin "2") (pinfunction "2_2") (pintype "passive"))
      (node (ref "R48") (pin "2") (pinfunction "2_2") (pintype "passive"))
      (node (ref "RN3") (pin "3") (pinfunction "3_3") (pintype "passive"))
      (node (ref "RN4") (pin "7") (pinfunction "1_7") (pintype "passive"))
      (node (ref "X4") (pin "7") (pinfunction "7_7") (pintype "passive"))
    )
    (net (code "92") (name "Net-(RN4G-2)") (class "Default")
      (node (ref "R35") (pin "1") (pinfunction "1_1") (pintype "passive"))
      (node (ref "RN4") (pin "10") (pinfunction "2_10") (pintype "passive"))
      (node (ref "U4") (pin "3") (pinfunction "B_3") (pintype "input"))
    )
    (net (code "93") (name "Net-(RN4H-1)") (class "Default")
      (node (ref "JP9") (pin "10") (pinfunction "10_10") (pintype "passive"))
      (node (ref "R34") (pin "2") (pinfunction "2_2") (pintype "passive"))
      (node (ref "R49") (pin "2") (pinfunction "2_2") (pintype "passive"))
      (node (ref "RN3") (pin "2") (pinfunction "2_2") (pintype "passive"))
      (node (ref "RN4") (pin "8") (pinfunction "1_8") (pintype "passive"))
      (node (ref "X4") (pin "8") (pinfunction "8_8") (pintype "passive"))
    )
    (net (code "94") (name "Net-(RN4H-2)") (class "Default")
      (node (ref "R34") (pin "1") (pinfunction "1_1") (pintype "passive"))
      (node (ref "RN4") (pin "9") (pinfunction "2_9") (pintype "passive"))
      (node (ref "U4") (pin "2") (pinfunction "A_2") (pintype "input"))
    )
    (net (code "95") (name "Net-(SJ1-1)") (class "Default")
      (node (ref "G1") (pin "PB14") (pinfunction "PB14_PB14") (pintype "bidirectional"))
      (node (ref "SJ1") (pin "P$1") (pinfunction "1_P$1") (pintype "passive"))
    )
    (net (code "96") (name "Net-(SJ2-1)") (class "Default")
      (node (ref "G1") (pin "VIN2") (pinfunction "VIN2_VIN2") (pintype "power_in"))
      (node (ref "SJ2") (pin "P$1") (pinfunction "1_P$1") (pintype "passive"))
    )
    (net (code "97") (name "Net-(SJ4-2)") (class "Default")
      (node (ref "JP5") (pin "2") (pinfunction "2_2") (pintype "passive"))
      (node (ref "SJ3") (pin "2") (pinfunction "2_2") (pintype "passive"))
      (node (ref "SJ4") (pin "P$2") (pinfunction "2_P$2") (pintype "passive"))
    )
    (net (code "98") (name "Net-(SJ7-1)") (class "Default")
      (node (ref "SJ11") (pin "1") (pinfunction "1_1") (pintype "passive"))
      (node (ref "SJ7") (pin "P$1") (pinfunction "1_P$1") (pintype "passive"))
      (node (ref "SJ9") (pin "P$1") (pinfunction "1_P$1") (pintype "passive"))
      (node (ref "U12") (pin "9") (pinfunction "GND_9") (pintype "power_in"))
    )
    (net (code "99") (name "Net-(SJ10-1)") (class "Default")
      (node (ref "SJ10") (pin "P$1") (pinfunction "1_P$1") (pintype "passive"))
      (node (ref "SJ12") (pin "P$1") (pinfunction "1_P$1") (pintype "passive"))
      (node (ref "SJ8") (pin "P$1") (pinfunction "1_P$1") (pintype "passive"))
      (node (ref "U12") (pin "10") (pinfunction "CD+_10") (pintype "passive"))
      (node (ref "X7") (pin "9") (pinfunction "9_9") (pintype "passive"))
    )
    (net (code "100") (name "Net-(SJ14-1)") (class "Default")
      (node (ref "SJ14") (pin "P$1") (pinfunction "1_P$1") (pintype "passive"))
      (node (ref "SJ16") (pin "P$1") (pinfunction "1_P$1") (pintype "passive"))
      (node (ref "SJ18") (pin "1") (pinfunction "1_1") (pintype "passive"))
      (node (ref "U14") (pin "9") (pinfunction "GND_9") (pintype "power_in"))
    )
    (net (code "101") (name "Net-(SJ15-1)") (class "Default")
      (node (ref "SJ15") (pin "P$1") (pinfunction "1_P$1") (pintype "passive"))
      (node (ref "SJ17") (pin "P$1") (pinfunction "1_P$1") (pintype "passive"))
      (node (ref "SJ19") (pin "P$1") (pinfunction "1_P$1") (pintype "passive"))
      (node (ref "U14") (pin "10") (pinfunction "CD+_10") (pintype "passive"))
      (node (ref "X8") (pin "9") (pinfunction "9_9") (pintype "passive"))
    )
    (net (code "102") (name "Net-(SJ20-2)") (class "Default")
      (node (ref "G1") (pin "PB13") (pinfunction "PB13_PB13") (pintype "bidirectional"))
      (node (ref "SJ20") (pin "P$2") (pinfunction "2_P$2") (pintype "passive"))
    )
    (net (code "103") (name "Net-(U5A-O)") (class "Default")
      (node (ref "JP10") (pin "1") (pinfunction "1_1") (pintype "passive"))
      (node (ref "U5") (pin "7") (pinfunction "O_7") (pintype "output"))
      (node (ref "U6") (pin "7") (pinfunction "OUT_7") (pintype "output"))
      (node (ref "X6") (pin "1") (pinfunction "1_1") (pintype "passive"))
    )
    (net (code "104") (name "Net-(U5B-O)") (class "Default")
      (node (ref "JP10") (pin "2") (pinfunction "2_2") (pintype "passive"))
      (node (ref "U5") (pin "5") (pinfunction "O_5") (pintype "output"))
      (node (ref "U6") (pin "8") (pinfunction "OUT_8") (pintype "output"))
      (node (ref "X6") (pin "2") (pinfunction "2_2") (pintype "passive"))
    )
    (net (code "105") (name "Net-(U6A--IN)") (class "Default")
      (node (ref "R50") (pin "1") (pinfunction "1_1") (pintype "passive"))
      (node (ref "R51") (pin "2") (pinfunction "2_2") (pintype "passive"))
      (node (ref "U6") (pin "13") (pinfunction "-IN_13") (pintype "input"))
      (node (ref "U6") (pin "2") (pinfunction "-IN_2") (pintype "input"))
      (node (ref "U6") (pin "6") (pinfunction "-IN_6") (pintype "input"))
      (node (ref "U6") (pin "9") (pinfunction "-IN_9") (pintype "input"))
      (node (ref "U9") (pin "13") (pinfunction "-IN_13") (pintype "input"))
      (node (ref "U9") (pin "2") (pinfunction "-IN_2") (pintype "input"))
      (node (ref "U9") (pin "6") (pinfunction "-IN_6") (pintype "input"))
      (node (ref "U9") (pin "9") (pinfunction "-IN_9") (pintype "input"))
    )
    (net (code "106") (name "Net-(U6A-OUT)") (class "Default")
      (node (ref "JP10") (pin "3") (pinfunction "3_3") (pintype "passive"))
      (node (ref "U6") (pin "1") (pinfunction "OUT_1") (pintype "output"))
      (node (ref "U7") (pin "5") (pinfunction "O_5") (pintype "output"))
      (node (ref "X6") (pin "3") (pinfunction "3_3") (pintype "passive"))
    )
    (net (code "107") (name "Net-(U6D-OUT)") (class "Default")
      (node (ref "JP10") (pin "4") (pinfunction "4_4") (pintype "passive"))
      (node (ref "U6") (pin "14") (pinfunction "OUT_14") (pintype "output"))
      (node (ref "U7") (pin "7") (pinfunction "O_7") (pintype "output"))
      (node (ref "X6") (pin "4") (pinfunction "4_4") (pintype "passive"))
    )
    (net (code "108") (name "Net-(U8A-O)") (class "Default")
      (node (ref "JP10") (pin "7") (pinfunction "7_7") (pintype "passive"))
      (node (ref "U8") (pin "7") (pinfunction "O_7") (pintype "output"))
      (node (ref "U9") (pin "7") (pinfunction "OUT_7") (pintype "output"))
      (node (ref "X6") (pin "5") (pinfunction "5_5") (pintype "passive"))
    )
    (net (code "109") (name "Net-(U8B-O)") (class "Default")
      (node (ref "JP10") (pin "8") (pinfunction "8_8") (pintype "passive"))
      (node (ref "U8") (pin "5") (pinfunction "O_5") (pintype "output"))
      (node (ref "U9") (pin "8") (pinfunction "OUT_8") (pintype "output"))
      (node (ref "X6") (pin "6") (pinfunction "6_6") (pintype "passive"))
    )
    (net (code "110") (name "Net-(U10A-O)") (class "Default")
      (node (ref "JP10") (pin "10") (pinfunction "10_10") (pintype "passive"))
      (node (ref "U10") (pin "7") (pinfunction "O_7") (pintype "output"))
      (node (ref "U9") (pin "14") (pinfunction "OUT_14") (pintype "output"))
      (node (ref "X6") (pin "8") (pinfunction "8_8") (pintype "passive"))
    )
    (net (code "111") (name "Net-(U10B-O)") (class "Default")
      (node (ref "JP10") (pin "9") (pinfunction "9_9") (pintype "passive"))
      (node (ref "U10") (pin "5") (pinfunction "O_5") (pintype "output"))
      (node (ref "U9") (pin "1") (pinfunction "OUT_1") (pintype "output"))
      (node (ref "X6") (pin "7") (pinfunction "7_7") (pintype "passive"))
    )
    (net (code "112") (name "Net-(U11A-QA)") (class "Default")
      (node (ref "R59") (pin "1") (pinfunction "1_1") (pintype "passive"))
      (node (ref "U11") (pin "15") (pinfunction "QA_15") (pintype "tri_state"))
      (node (ref "U12") (pin "1") (pinfunction "I1_1") (pintype "input"))
    )
    (net (code "113") (name "Net-(U11A-QB)") (class "Default")
      (node (ref "R58") (pin "1") (pinfunction "1_1") (pintype "passive"))
      (node (ref "U11") (pin "1") (pinfunction "QB_1") (pintype "tri_state"))
      (node (ref "U12") (pin "2") (pinfunction "I2_2") (pintype "input"))
    )
    (net (code "114") (name "Net-(U11A-QC)") (class "Default")
      (node (ref "R57") (pin "1") (pinfunction "1_1") (pintype "passive"))
      (node (ref "U11") (pin "2") (pinfunction "QC_2") (pintype "tri_state"))
      (node (ref "U12") (pin "3") (pinfunction "I3_3") (pintype "input"))
    )
    (net (code "115") (name "Net-(U11A-QD)") (class "Default")
      (node (ref "R56") (pin "1") (pinfunction "1_1") (pintype "passive"))
      (node (ref "U11") (pin "3") (pinfunction "QD_3") (pintype "tri_state"))
      (node (ref "U12") (pin "4") (pinfunction "I4_4") (pintype "input"))
    )
    (net (code "116") (name "Net-(U11A-QE)") (class "Default")
      (node (ref "R55") (pin "1") (pinfunction "1_1") (pintype "passive"))
      (node (ref "U11") (pin "4") (pinfunction "QE_4") (pintype "tri_state"))
      (node (ref "U12") (pin "5") (pinfunction "I5_5") (pintype "input"))
    )
    (net (code "117") (name "Net-(U11A-QF)") (class "Default")
      (node (ref "R54") (pin "1") (pinfunction "1_1") (pintype "passive"))
      (node (ref "U11") (pin "5") (pinfunction "QF_5") (pintype "tri_state"))
      (node (ref "U12") (pin "6") (pinfunction "I6_6") (pintype "input"))
    )
    (net (code "118") (name "Net-(U11A-QG)") (class "Default")
      (node (ref "R53") (pin "1") (pinfunction "1_1") (pintype "passive"))
      (node (ref "U11") (pin "6") (pinfunction "QG_6") (pintype "tri_state"))
      (node (ref "U12") (pin "7") (pinfunction "I7_7") (pintype "input"))
    )
    (net (code "119") (name "Net-(U11A-QH)") (class "Default")
      (node (ref "R52") (pin "1") (pinfunction "1_1") (pintype "passive"))
      (node (ref "U11") (pin "7") (pinfunction "QH_7") (pintype "tri_state"))
      (node (ref "U12") (pin "8") (pinfunction "I8_8") (pintype "input"))
    )
    (net (code "120") (name "Net-(U13A-QA)") (class "Default")
      (node (ref "R67") (pin "1") (pinfunction "1_1") (pintype "passive"))
      (node (ref "U13") (pin "15") (pinfunction "QA_15") (pintype "tri_state"))
      (node (ref "U14") (pin "1") (pinfunction "I1_1") (pintype "input"))
    )
    (net (code "121") (name "Net-(U13A-QB)") (class "Default")
      (node (ref "R66") (pin "1") (pinfunction "1_1") (pintype "passive"))
      (node (ref "U13") (pin "1") (pinfunction "QB_1") (pintype "tri_state"))
      (node (ref "U14") (pin "2") (pinfunction "I2_2") (pintype "input"))
    )
    (net (code "122") (name "Net-(U13A-QC)") (class "Default")
      (node (ref "R65") (pin "1") (pinfunction "1_1") (pintype "passive"))
      (node (ref "U13") (pin "2") (pinfunction "QC_2") (pintype "tri_state"))
      (node (ref "U14") (pin "3") (pinfunction "I3_3") (pintype "input"))
    )
    (net (code "123") (name "Net-(U13A-QD)") (class "Default")
      (node (ref "R64") (pin "1") (pinfunction "1_1") (pintype "passive"))
      (node (ref "U13") (pin "3") (pinfunction "QD_3") (pintype "tri_state"))
      (node (ref "U14") (pin "4") (pinfunction "I4_4") (pintype "input"))
    )
    (net (code "124") (name "Net-(U13A-QE)") (class "Default")
      (node (ref "R63") (pin "1") (pinfunction "1_1") (pintype "passive"))
      (node (ref "U13") (pin "4") (pinfunction "QE_4") (pintype "tri_state"))
      (node (ref "U14") (pin "5") (pinfunction "I5_5") (pintype "input"))
    )
    (net (code "125") (name "Net-(U13A-QF)") (class "Default")
      (node (ref "R62") (pin "1") (pinfunction "1_1") (pintype "passive"))
      (node (ref "U13") (pin "5") (pinfunction "QF_5") (pintype "tri_state"))
      (node (ref "U14") (pin "6") (pinfunction "I6_6") (pintype "input"))
    )
    (net (code "126") (name "Net-(U13A-QG)") (class "Default")
      (node (ref "R61") (pin "1") (pinfunction "1_1") (pintype "passive"))
      (node (ref "U13") (pin "6") (pinfunction "QG_6") (pintype "tri_state"))
      (node (ref "U14") (pin "7") (pinfunction "I7_7") (pintype "input"))
    )
    (net (code "127") (name "Net-(U13A-QH)") (class "Default")
      (node (ref "R60") (pin "1") (pinfunction "1_1") (pintype "passive"))
      (node (ref "U13") (pin "7") (pinfunction "QH_7") (pintype "tri_state"))
      (node (ref "U14") (pin "8") (pinfunction "I8_8") (pintype "input"))
    )
    (net (code "128") (name "Net-(X1-Pad4)") (class "Default")
      (node (ref "X1") (pin "4") (pinfunction "4_4") (pintype "passive"))
      (node (ref "X2") (pin "4") (pinfunction "4_4") (pintype "passive"))
    )
    (net (code "129") (name "Net-(X1-Pad5)") (class "Default")
      (node (ref "X1") (pin "5") (pinfunction "5_5") (pintype "passive"))
      (node (ref "X2") (pin "5") (pinfunction "5_5") (pintype "passive"))
    )
    (net (code "130") (name "OLAT") (class "Default")
      (node (ref "G1") (pin "PA8") (pinfunction "PA8_PA8") (pintype "bidirectional"))
      (node (ref "R3") (pin "1") (pinfunction "1_1") (pintype "passive"))
      (node (ref "U11") (pin "12") (pinfunction "RCK_12") (pintype "input"))
      (node (ref "U13") (pin "12") (pinfunction "RCK_12") (pintype "input"))
    )
    (net (code "131") (name "SCK") (class "Default")
      (node (ref "G1") (pin "PB3") (pinfunction "PB3_PB3") (pintype "bidirectional"))
      (node (ref "JP5") (pin "3") (pinfunction "3_3") (pintype "passive"))
      (node (ref "R5") (pin "1") (pinfunction "1_1") (pintype "passive"))
      (node (ref "U11") (pin "11") (pinfunction "SCK_11") (pintype "input"))
      (node (ref "U13") (pin "11") (pinfunction "SCK_11") (pintype "input"))
    )
    (net (code "132") (name "SCK2") (class "Default")
      (node (ref "G1") (pin "PB10") (pinfunction "PB10_PB10") (pintype "bidirectional"))
      (node (ref "SJ20") (pin "P$1") (pinfunction "1_P$1") (pintype "passive"))
      (node (ref "U3") (pin "7") (pinfunction "CLK_7") (pintype "input"))
      (node (ref "U4") (pin "7") (pinfunction "CLK_7") (pintype "input"))
    )
    (net (code "133") (name "SLNK1") (class "Default")
      (node (ref "SJ13") (pin "P$1") (pinfunction "1_P$1") (pintype "passive"))
      (node (ref "U11") (pin "14") (pinfunction "SER_14") (pintype "input"))
      (node (ref "U13") (pin "9") (pinfunction "QH*_9") (pintype "tri_state"))
    )
    (net (code "134") (name "SLNK2") (class "Default")
      (node (ref "SJ4") (pin "P$1") (pinfunction "1_P$1") (pintype "passive"))
      (node (ref "U11") (pin "9") (pinfunction "QH*_9") (pintype "tri_state"))
    )
    (net (code "135") (name "SLNK3") (class "Default")
      (node (ref "SJ6") (pin "P$1") (pinfunction "1_P$1") (pintype "passive"))
      (node (ref "U3") (pin "1") (pinfunction "SER_1") (pintype "input"))
      (node (ref "U4") (pin "13") (pinfunction "QH_13") (pintype "output"))
    )
    (net (code "136") (name "SRV1") (class "Default")
      (node (ref "G1") (pin "PC9") (pinfunction "PC9_PC9") (pintype "bidirectional"))
      (node (ref "JP4") (pin "2") (pinfunction "2_2") (pintype "passive"))
      (node (ref "R13") (pin "2") (pinfunction "2_2") (pintype "passive"))
    )
    (net (code "137") (name "SRV2") (class "Default")
      (node (ref "G1") (pin "PC7") (pinfunction "PC7_PC7") (pintype "bidirectional"))
      (node (ref "JP4") (pin "1") (pinfunction "1_1") (pintype "passive"))
      (node (ref "R12") (pin "2") (pinfunction "2_2") (pintype "passive"))
    )
    (net (code "138") (name "SRV3") (class "Default")
      (node (ref "G1") (pin "PC8") (pinfunction "PC8_PC8") (pintype "bidirectional"))
      (node (ref "JP3") (pin "2") (pinfunction "2_2") (pintype "passive"))
      (node (ref "R11") (pin "2") (pinfunction "2_2") (pintype "passive"))
    )
    (net (code "139") (name "SRV4") (class "Default")
      (node (ref "G1") (pin "PC6") (pinfunction "PC6_PC6") (pintype "bidirectional"))
      (node (ref "JP3") (pin "1") (pinfunction "1_1") (pintype "passive"))
      (node (ref "R10") (pin "2") (pinfunction "2_2") (pintype "passive"))
    )
    (net (code "140") (name "SRV5") (class "Default")
      (node (ref "G1") (pin "PF1-PH1") (pinfunction "PF1-PH1_PF1-PH1") (pintype "bidirectional"))
      (node (ref "JP2") (pin "2") (pinfunction "2_2") (pintype "passive"))
      (node (ref "R9") (pin "2") (pinfunction "2_2") (pintype "passive"))
    )
    (net (code "141") (name "SRV6") (class "Default")
      (node (ref "G1") (pin "PA15") (pinfunction "PA15_PA15") (pintype "bidirectional"))
      (node (ref "JP2") (pin "1") (pinfunction "1_1") (pintype "passive"))
      (node (ref "R8") (pin "2") (pinfunction "2_2") (pintype "passive"))
    )
    (net (code "142") (name "SRV7") (class "Default")
      (node (ref "G1") (pin "PC12") (pinfunction "PC12_PC12") (pintype "bidirectional"))
      (node (ref "JP1") (pin "2") (pinfunction "2_2") (pintype "passive"))
      (node (ref "R7") (pin "2") (pinfunction "2_2") (pintype "passive"))
    )
    (net (code "143") (name "SRV8") (class "Default")
      (node (ref "G1") (pin "PD2") (pinfunction "PD2_PD2") (pintype "bidirectional"))
      (node (ref "JP1") (pin "1") (pinfunction "1_1") (pintype "passive"))
      (node (ref "R6") (pin "2") (pinfunction "2_2") (pintype "passive"))
    )
    (net (code "144") (name "TDRV1") (class "Default")
      (node (ref "G1") (pin "PB12") (pinfunction "PB12_PB12") (pintype "bidirectional"))
      (node (ref "U10") (pin "2") (pinfunction "I_2") (pintype "input"))
      (node (ref "U9") (pin "12") (pinfunction "+IN_12") (pintype "input"))
    )
    (net (code "145") (name "TDRV2") (class "Default")
      (node (ref "G1") (pin "PB2") (pinfunction "PB2_PB2") (pintype "bidirectional"))
      (node (ref "U10") (pin "4") (pinfunction "I_4") (pintype "input"))
      (node (ref "U9") (pin "3") (pinfunction "+IN_3") (pintype "input"))
    )
    (net (code "146") (name "TDRV3") (class "Default")
      (node (ref "G1") (pin "PB15") (pinfunction "PB15_PB15") (pintype "bidirectional"))
      (node (ref "U8") (pin "4") (pinfunction "I_4") (pintype "input"))
      (node (ref "U9") (pin "10") (pinfunction "+IN_10") (pintype "input"))
    )
    (net (code "147") (name "TDRV4") (class "Default")
      (node (ref "G1") (pin "PB1") (pinfunction "PB1_PB1") (pintype "bidirectional"))
      (node (ref "U8") (pin "2") (pinfunction "I_2") (pintype "input"))
      (node (ref "U9") (pin "5") (pinfunction "+IN_5") (pintype "input"))
    )
    (net (code "148") (name "TDRV5") (class "Default")
      (node (ref "G1") (pin "PA0") (pinfunction "PA0_PA0") (pintype "bidirectional"))
      (node (ref "U6") (pin "12") (pinfunction "+IN_12") (pintype "input"))
      (node (ref "U7") (pin "2") (pinfunction "I_2") (pintype "input"))
    )
    (net (code "149") (name "TDRV6") (class "Default")
      (node (ref "G1") (pin "PA4") (pinfunction "PA4_PA4") (pintype "bidirectional"))
      (node (ref "U6") (pin "3") (pinfunction "+IN_3") (pintype "input"))
      (node (ref "U7") (pin "4") (pinfunction "I_4") (pintype "input"))
    )
    (net (code "150") (name "TDRV7") (class "Default")
      (node (ref "G1") (pin "PC3") (pinfunction "PC3_PC3") (pintype "bidirectional"))
      (node (ref "U5") (pin "4") (pinfunction "I_4") (pintype "input"))
      (node (ref "U6") (pin "10") (pinfunction "+IN_10") (pintype "input"))
    )
    (net (code "151") (name "TDRV8") (class "Default")
      (node (ref "G1") (pin "PC0") (pinfunction "PC0_PC0") (pintype "bidirectional"))
      (node (ref "U5") (pin "2") (pinfunction "I_2") (pintype "input"))
      (node (ref "U6") (pin "5") (pinfunction "+IN_5") (pintype "input"))
    )
    (net (code "152") (name "V+") (class "Default")
      (node (ref "C6") (pin "+") (pinfunction "+_+") (pintype "passive"))
      (node (ref "C7") (pin "1") (pinfunction "1_1") (pintype "passive"))
      (node (ref "G1") (pin "E5V") (pinfunction "E5V_E5V") (pintype "power_in"))
      (node (ref "IC1") (pin "1") (pinfunction "FB_1") (pintype "input"))
      (node (ref "L1") (pin "1") (pinfunction "1_1") (pintype "passive"))
      (node (ref "U2") (pin "3") (pinfunction "FB_3") (pintype "bidirectional"))
    )
    (net (code "153") (name "unconnected-(G1-PadBOOT0)") (class "Default")
      (node (ref "G1") (pin "BOOT0") (pinfunction "BOOT0_BOOT0") (pintype "bidirectional"))
    )
    (net (code "154") (name "unconnected-(G1-PadIOREF2)") (class "Default")
      (node (ref "G1") (pin "IOREF2") (pinfunction "IOREF2_IOREF2") (pintype "input"))
    )
    (net (code "155") (name "unconnected-(G1-PadNC1-PF7)") (class "Default")
      (node (ref "G1") (pin "NC1-PF7") (pinfunction "NC1-PF7_NC1-PF7") (pintype "bidirectional"))
    )
    (net (code "156") (name "unconnected-(G1-PadNC2-PF6)") (class "Default")
      (node (ref "G1") (pin "NC2-PF6") (pinfunction "NC2-PF6_NC2-PF6") (pintype "bidirectional"))
    )
    (net (code "157") (name "unconnected-(G1-PadNC3)") (class "Default")
      (node (ref "G1") (pin "NC3") (pinfunction "NC3_NC3") (pintype "no_connect"))
    )
    (net (code "158") (name "unconnected-(G1-PadNC4)") (class "Default")
      (node (ref "G1") (pin "NC4") (pinfunction "NC4_NC4") (pintype "no_connect"))
    )
    (net (code "159") (name "unconnected-(G1-PadNC5-PD8)") (class "Default")
      (node (ref "G1") (pin "NC5-PD8") (pinfunction "NC5-PD8_NC5-PD8") (pintype "bidirectional"))
    )
    (net (code "160") (name "unconnected-(G1-PadNC6-PB11)") (class "Default")
      (node (ref "G1") (pin "NC6-PB11") (pinfunction "NC6-PB11_NC6-PB11") (pintype "no_connect"))
    )
    (net (code "161") (name "unconnected-(G1-PadNC7-PF5)") (class "Default")
      (node (ref "G1") (pin "NC7-PF5") (pinfunction "NC7-PF5_NC7-PF5") (pintype "bidirectional"))
    )
    (net (code "162") (name "unconnected-(G1-PadNC8-PF4)") (class "Default")
      (node (ref "G1") (pin "NC8-PF4") (pinfunction "NC8-PF4_NC8-PF4") (pintype "bidirectional"))
    )
    (net (code "163") (name "unconnected-(G1-PadNRESET)") (class "Default")
      (node (ref "G1") (pin "NRESET") (pinfunction "NRESET_NRESET") (pintype "input"))
    )
    (net (code "164") (name "unconnected-(G1-PadPA1)") (class "Default")
      (node (ref "G1") (pin "PA1") (pinfunction "PA1_PA1") (pintype "bidirectional"))
    )
    (net (code "165") (name "unconnected-(G1-PadPA2)") (class "Default")
      (node (ref "G1") (pin "PA2") (pinfunction "PA2_PA2") (pintype "bidirectional"))
    )
    (net (code "166") (name "unconnected-(G1-PadPA3)") (class "Default")
      (node (ref "G1") (pin "PA3") (pinfunction "PA3_PA3") (pintype "bidirectional"))
    )
    (net (code "167") (name "unconnected-(G1-PadPA5)") (class "Default")
      (node (ref "G1") (pin "PA5") (pinfunction "PA5_PA5") (pintype "bidirectional"))
    )
    (net (code "168") (name "unconnected-(G1-PadPA7)") (class "Default")
      (node (ref "G1") (pin "PA7") (pinfunction "PA7_PA7") (pintype "bidirectional"))
    )
    (net (code "169") (name "unconnected-(G1-PadPA9)") (class "Default")
      (node (ref "G1") (pin "PA9") (pinfunction "PA9_PA9") (pintype "bidirectional"))
    )
    (net (code "170") (name "unconnected-(G1-PadPA10)") (class "Default")
      (node (ref "G1") (pin "PA10") (pinfunction "PA10_PA10") (pintype "bidirectional"))
    )
    (net (code "171") (name "unconnected-(G1-PadPA11)") (class "Default")
      (node (ref "G1") (pin "PA11") (pinfunction "PA11_PA11") (pintype "bidirectional"))
    )
    (net (code "172") (name "unconnected-(G1-PadPA12)") (class "Default")
      (node (ref "G1") (pin "PA12") (pinfunction "PA12_PA12") (pintype "bidirectional"))
    )
    (net (code "173") (name "unconnected-(G1-PadPA13)") (class "Default")
      (node (ref "G1") (pin "PA13") (pinfunction "PA13_PA13") (pintype "bidirectional"))
    )
    (net (code "174") (name "unconnected-(G1-PadPA14)") (class "Default")
      (node (ref "G1") (pin "PA14") (pinfunction "PA14_PA14") (pintype "bidirectional"))
    )
    (net (code "175") (name "unconnected-(G1-PadPB0)") (class "Default")
      (node (ref "G1") (pin "PB0") (pinfunction "PB0_PB0") (pintype "bidirectional"))
    )
    (net (code "176") (name "unconnected-(G1-PadPC1)") (class "Default")
      (node (ref "G1") (pin "PC1") (pinfunction "PC1_PC1") (pintype "bidirectional"))
    )
    (net (code "177") (name "unconnected-(G1-PadPC4)") (class "Default")
      (node (ref "G1") (pin "PC4") (pinfunction "PC4_PC4") (pintype "bidirectional"))
    )
    (net (code "178") (name "unconnected-(G1-PadPC5)") (class "Default")
      (node (ref "G1") (pin "PC5") (pinfunction "PC5_PC5") (pintype "bidirectional"))
    )
    (net (code "179") (name "unconnected-(G1-PadPC13)") (class "Default")
      (node (ref "G1") (pin "PC13") (pinfunction "PC13_PC13") (pintype "bidirectional"))
    )
    (net (code "180") (name "unconnected-(G1-PadPC14)") (class "Default")
      (node (ref "G1") (pin "PC14") (pinfunction "PC14_PC14") (pintype "bidirectional"))
    )
    (net (code "181") (name "unconnected-(G1-PadPC15)") (class "Default")
      (node (ref "G1") (pin "PC15") (pinfunction "PC15_PC15") (pintype "bidirectional"))
    )
    (net (code "182") (name "unconnected-(G1-PadPF0-PH0)") (class "Default")
      (node (ref "G1") (pin "PF0-PH0") (pinfunction "PF0-PH0_PF0-PH0") (pintype "bidirectional"))
    )
    (net (code "183") (name "unconnected-(H1-MOUNT-PadB3,3)") (class "Default")
      (node (ref "H1") (pin "B3,3") (pinfunction "MOUNT_B3,3") (pintype "passive"))
    )
    (net (code "184") (name "unconnected-(H2-MOUNT-PadB3,3)") (class "Default")
      (node (ref "H2") (pin "B3,3") (pinfunction "MOUNT_B3,3") (pintype "passive"))
    )
    (net (code "185") (name "unconnected-(H3-MOUNT-PadB3,3)") (class "Default")
      (node (ref "H3") (pin "B3,3") (pinfunction "MOUNT_B3,3") (pintype "passive"))
    )
    (net (code "186") (name "unconnected-(H4-MOUNT-PadB3,3)") (class "Default")
      (node (ref "H4") (pin "B3,3") (pinfunction "MOUNT_B3,3") (pintype "passive"))
    )
  )
)
